# keyboard.net
KiCad netlist of a schematic drawn in Altium Designer
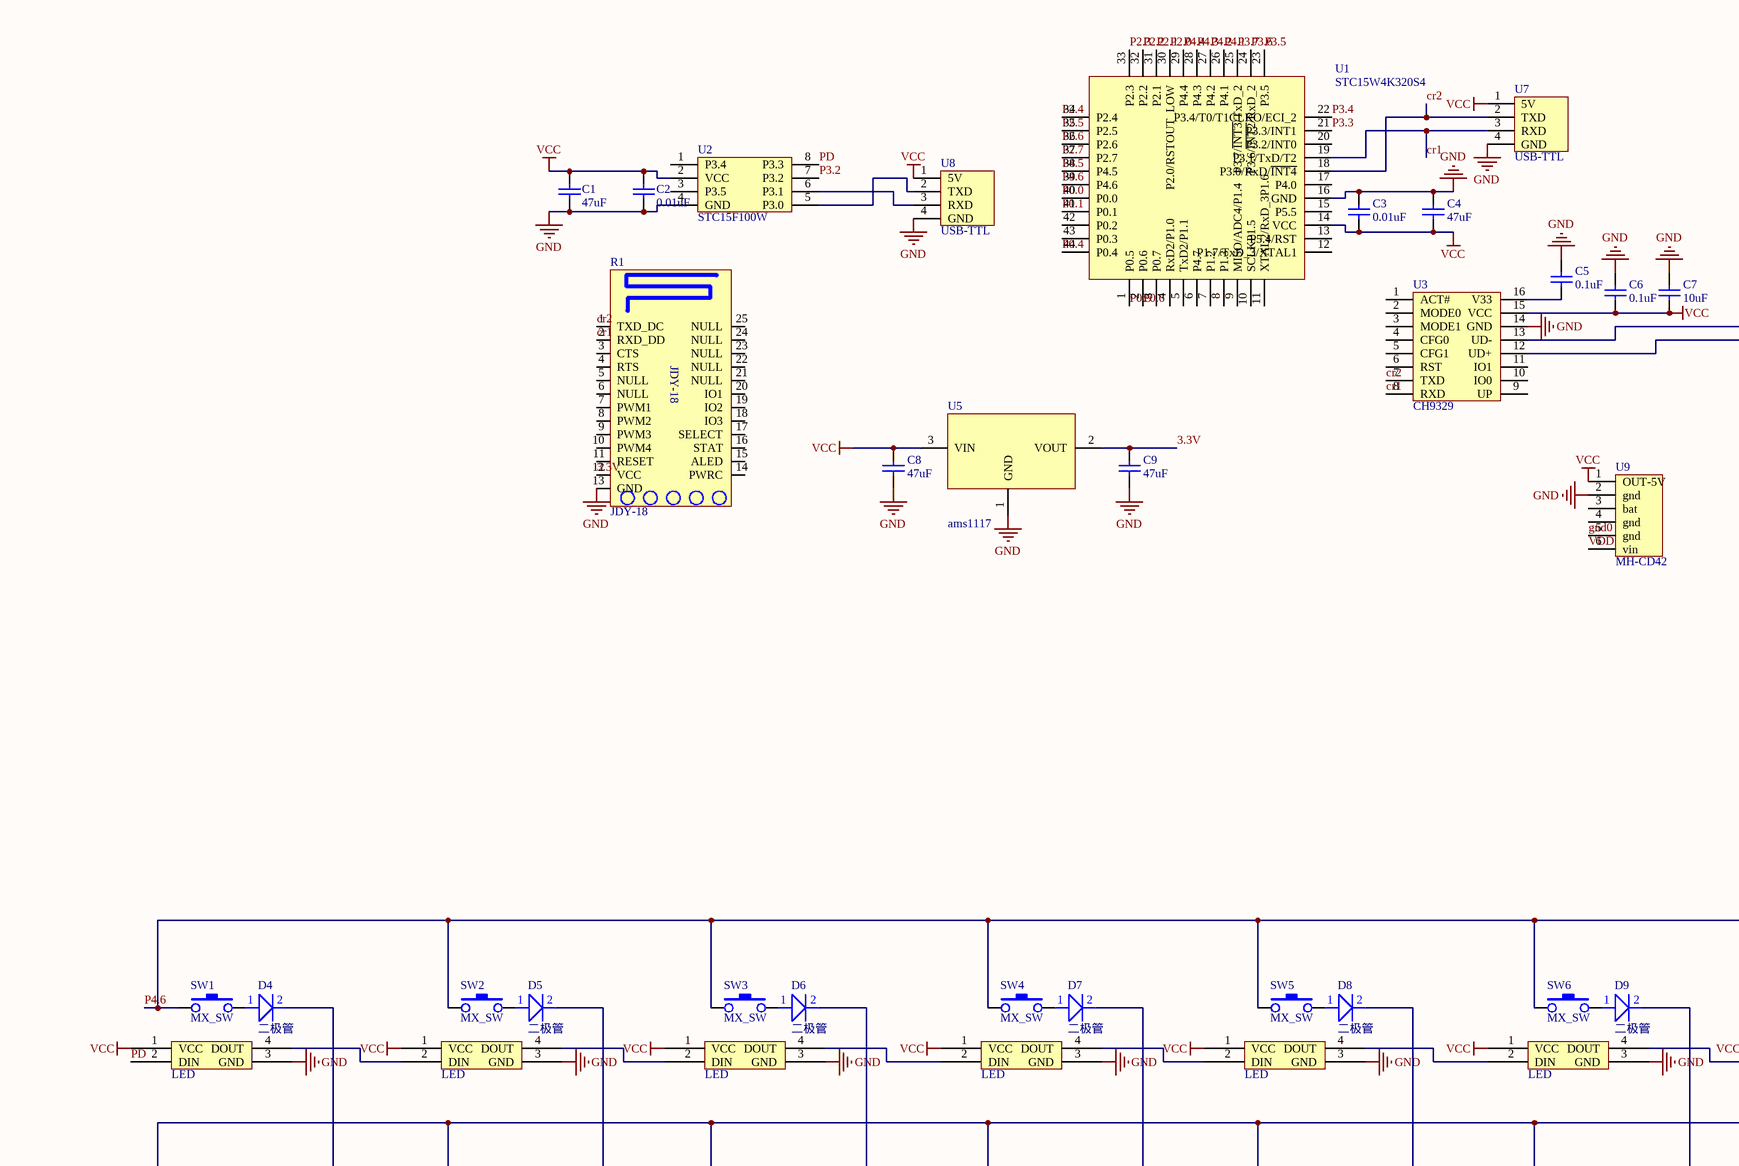
[diagram p0: keyboard.SchDoc, top left]
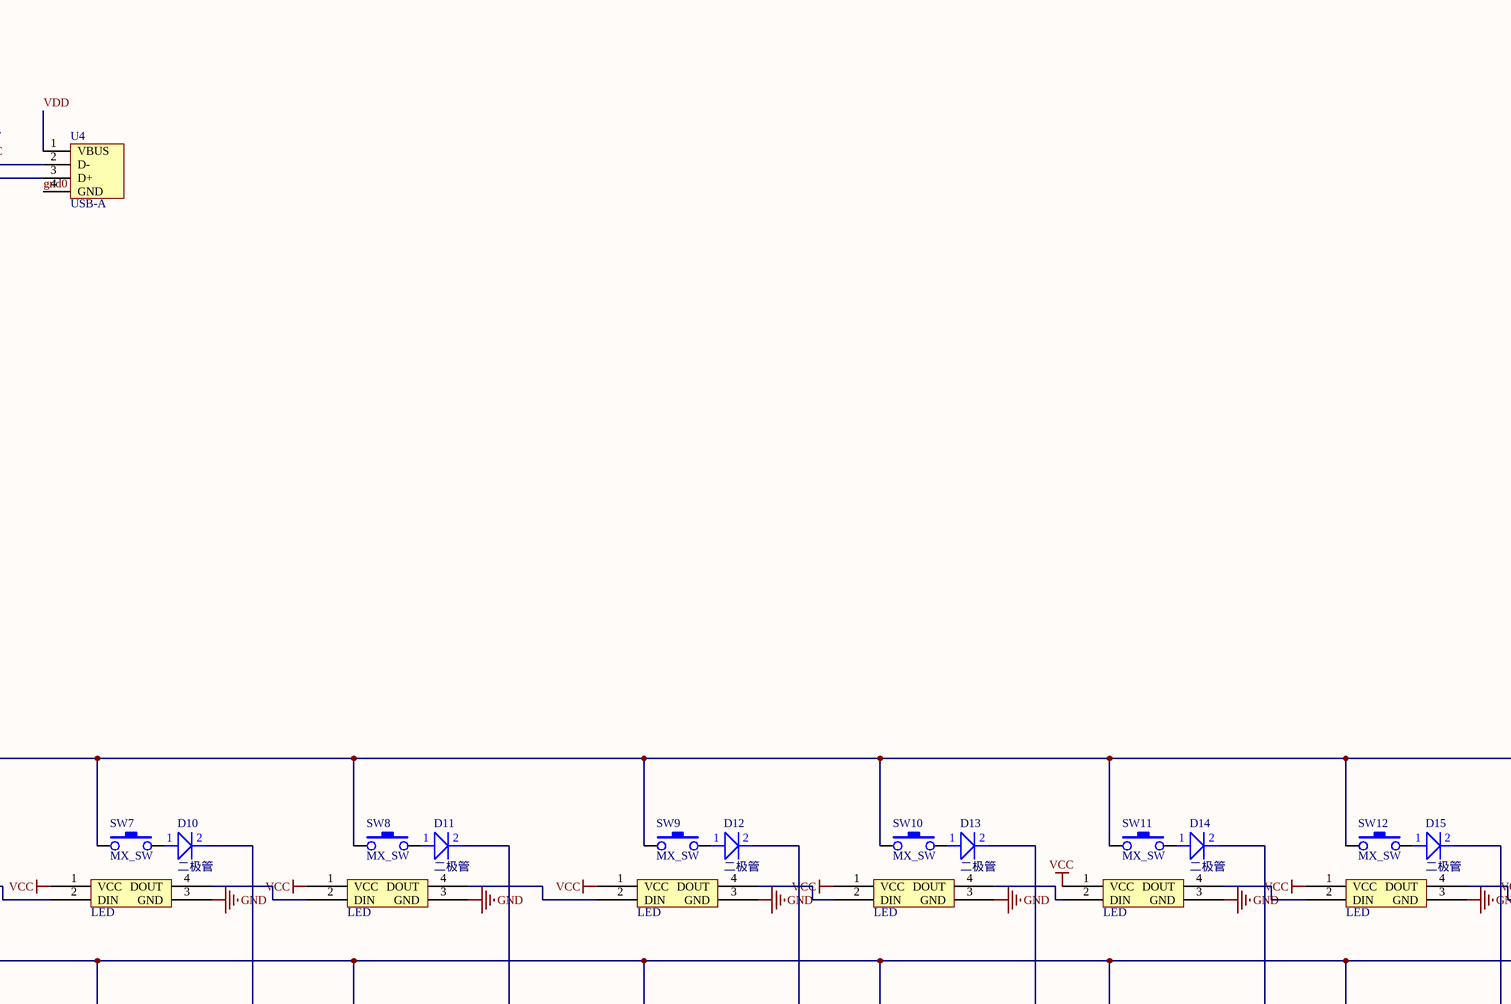
[diagram p1: keyboard.SchDoc, top middle]
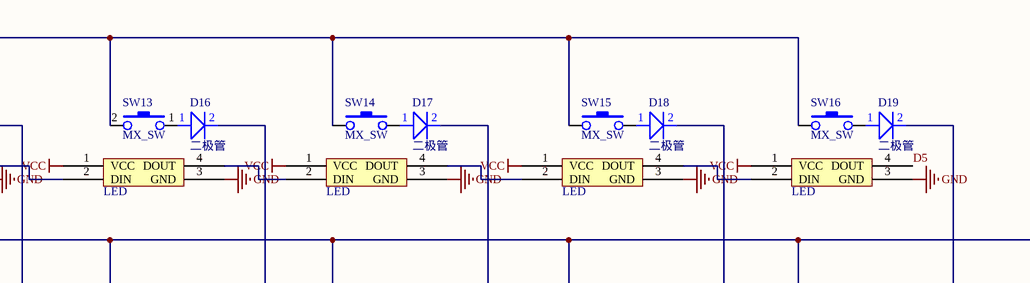
[diagram p2: keyboard.SchDoc, top right]
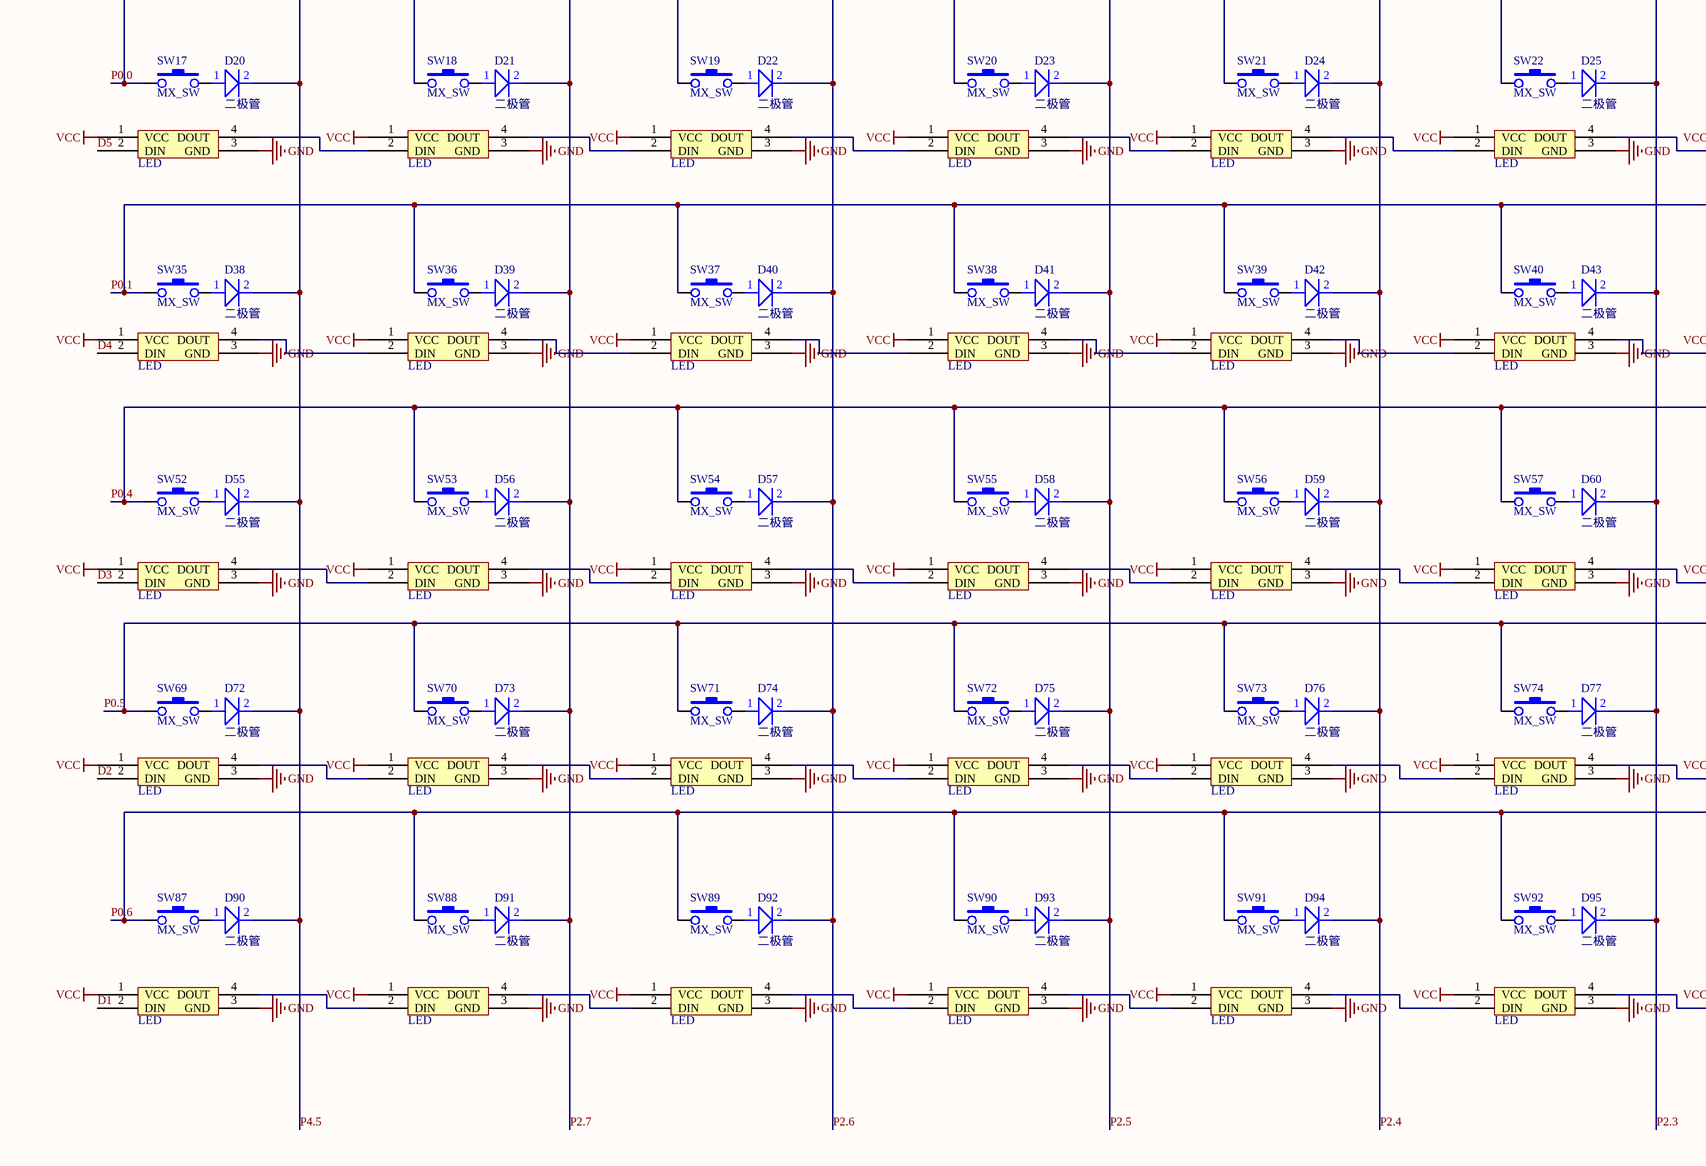
[diagram p3: keyboard.SchDoc, bottom left]
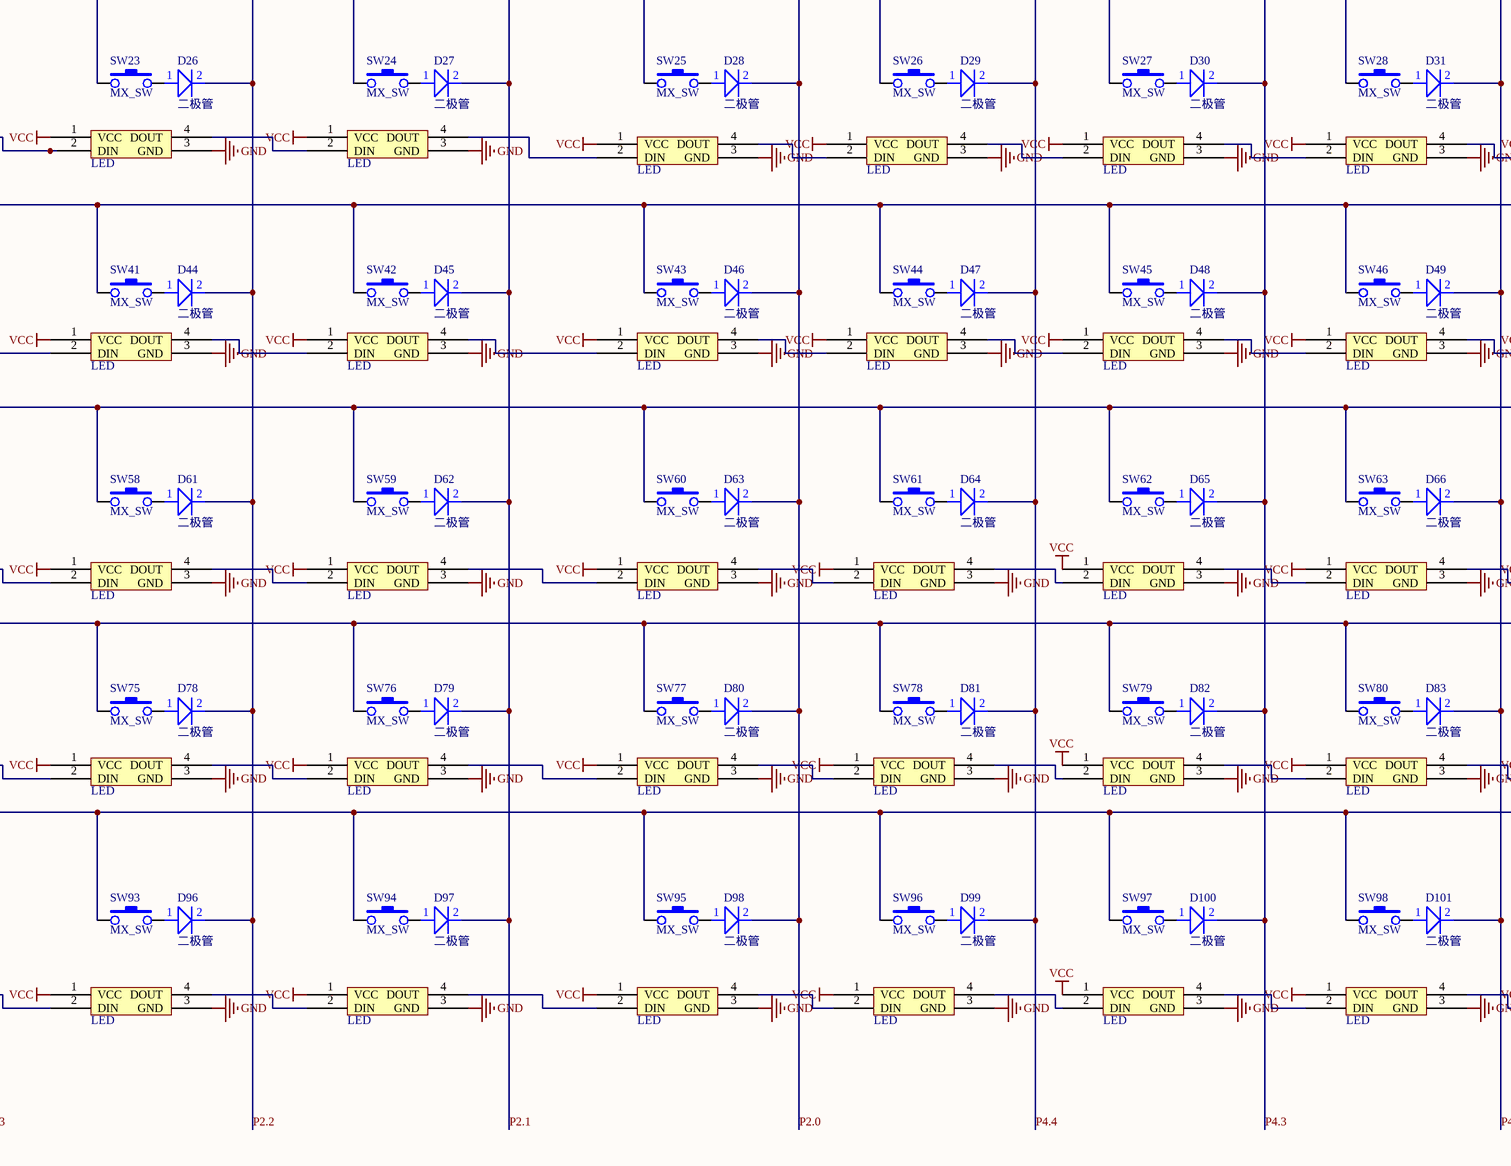
[diagram p4: keyboard.SchDoc, bottom middle]
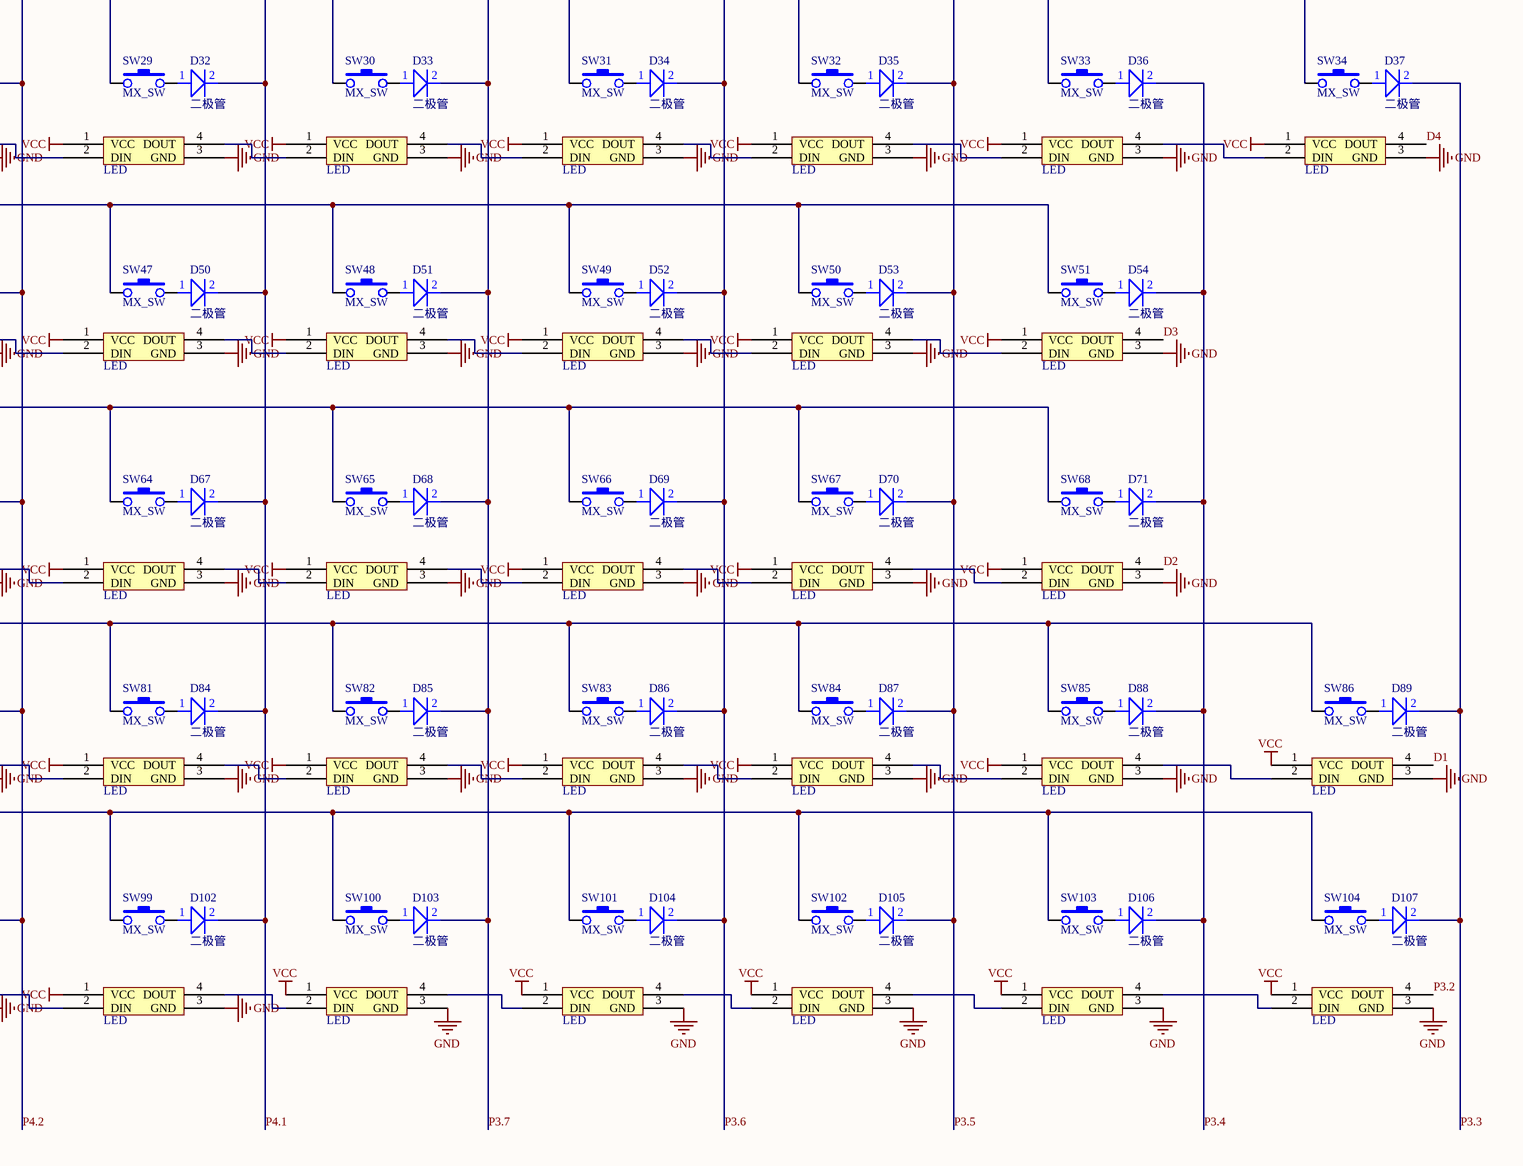
[diagram p5: keyboard.SchDoc, bottom right]

(export (version "E")
  (design (tool "Eeschema 10.0.6"))
  (components
    (comp (ref "*1") (value "LED") (footprint "6028") (libsource (lib "KeyBoard") (part "3512led")))
    (comp (ref "*2") (value "LED") (footprint "6028") (libsource (lib "KeyBoard") (part "3512led")))
    (comp (ref "*3") (value "LED") (footprint "6028") (libsource (lib "KeyBoard") (part "3512led")))
    (comp (ref "*4") (value "LED") (footprint "6028") (libsource (lib "KeyBoard") (part "3512led")))
    (comp (ref "*5") (value "LED") (footprint "6028") (libsource (lib "KeyBoard") (part "3512led")))
    (comp (ref "*6") (value "LED") (footprint "6028") (libsource (lib "KeyBoard") (part "3512led")))
    (comp (ref "*7") (value "LED") (footprint "6028") (libsource (lib "KeyBoard") (part "3512led")))
    (comp (ref "*8") (value "LED") (footprint "6028") (libsource (lib "KeyBoard") (part "3512led")))
    (comp (ref "*9") (value "LED") (footprint "6028") (libsource (lib "KeyBoard") (part "3512led")))
    (comp (ref "*10") (value "LED") (footprint "6028") (libsource (lib "KeyBoard") (part "3512led")))
    (comp (ref "*11") (value "LED") (footprint "6028") (libsource (lib "KeyBoard") (part "3512led")))
    (comp (ref "*12") (value "LED") (footprint "6028") (libsource (lib "KeyBoard") (part "3512led")))
    (comp (ref "*13") (value "LED") (footprint "6028") (libsource (lib "KeyBoard") (part "3512led")))
    (comp (ref "*14") (value "LED") (footprint "6028") (libsource (lib "KeyBoard") (part "3512led")))
    (comp (ref "*15") (value "LED") (footprint "6028") (libsource (lib "KeyBoard") (part "3512led")))
    (comp (ref "*16") (value "LED") (footprint "6028") (libsource (lib "KeyBoard") (part "3512led")))
    (comp (ref "*17") (value "LED") (footprint "6028") (libsource (lib "KeyBoard") (part "3512led")))
    (comp (ref "*18") (value "LED") (footprint "6028") (libsource (lib "KeyBoard") (part "3512led")))
    (comp (ref "*19") (value "LED") (footprint "6028") (libsource (lib "KeyBoard") (part "3512led")))
    (comp (ref "*20") (value "LED") (footprint "6028") (libsource (lib "KeyBoard") (part "3512led")))
    (comp (ref "*21") (value "LED") (footprint "6028") (libsource (lib "KeyBoard") (part "3512led")))
    (comp (ref "*22") (value "LED") (footprint "6028") (libsource (lib "KeyBoard") (part "3512led")))
    (comp (ref "*23") (value "LED") (footprint "6028") (libsource (lib "KeyBoard") (part "3512led")))
    (comp (ref "*24") (value "LED") (footprint "6028") (libsource (lib "KeyBoard") (part "3512led")))
    (comp (ref "*25") (value "LED") (footprint "6028") (libsource (lib "KeyBoard") (part "3512led")))
    (comp (ref "*26") (value "LED") (footprint "6028") (libsource (lib "KeyBoard") (part "3512led")))
    (comp (ref "*27") (value "LED") (footprint "6028") (libsource (lib "KeyBoard") (part "3512led")))
    (comp (ref "*28") (value "LED") (footprint "6028") (libsource (lib "KeyBoard") (part "3512led")))
    (comp (ref "*29") (value "LED") (footprint "6028") (libsource (lib "KeyBoard") (part "3512led")))
    (comp (ref "*30") (value "LED") (footprint "6028") (libsource (lib "KeyBoard") (part "3512led")))
    (comp (ref "*31") (value "LED") (footprint "6028") (libsource (lib "KeyBoard") (part "3512led")))
    (comp (ref "*32") (value "LED") (footprint "6028") (libsource (lib "KeyBoard") (part "3512led")))
    (comp (ref "*33") (value "LED") (footprint "6028") (libsource (lib "KeyBoard") (part "3512led")))
    (comp (ref "*34") (value "LED") (footprint "6028") (libsource (lib "KeyBoard") (part "3512led")))
    (comp (ref "*35") (value "LED") (footprint "6028") (libsource (lib "KeyBoard") (part "3512led")))
    (comp (ref "*36") (value "LED") (footprint "6028") (libsource (lib "KeyBoard") (part "3512led")))
    (comp (ref "*37") (value "LED") (footprint "6028") (libsource (lib "KeyBoard") (part "3512led")))
    (comp (ref "*38") (value "LED") (footprint "6028") (libsource (lib "KeyBoard") (part "3512led")))
    (comp (ref "*39") (value "LED") (footprint "6028") (libsource (lib "KeyBoard") (part "3512led")))
    (comp (ref "*40") (value "LED") (footprint "6028") (libsource (lib "KeyBoard") (part "3512led")))
    (comp (ref "*41") (value "LED") (footprint "6028") (libsource (lib "KeyBoard") (part "3512led")))
    (comp (ref "*42") (value "LED") (footprint "6028") (libsource (lib "KeyBoard") (part "3512led")))
    (comp (ref "*43") (value "LED") (footprint "6028") (libsource (lib "KeyBoard") (part "3512led")))
    (comp (ref "*44") (value "LED") (footprint "6028") (libsource (lib "KeyBoard") (part "3512led")))
    (comp (ref "*45") (value "LED") (footprint "6028") (libsource (lib "KeyBoard") (part "3512led")))
    (comp (ref "*46") (value "LED") (footprint "6028") (libsource (lib "KeyBoard") (part "3512led")))
    (comp (ref "*47") (value "LED") (footprint "6028") (libsource (lib "KeyBoard") (part "3512led")))
    (comp (ref "*48") (value "LED") (footprint "6028") (libsource (lib "KeyBoard") (part "3512led")))
    (comp (ref "*49") (value "LED") (footprint "6028") (libsource (lib "KeyBoard") (part "3512led")))
    (comp (ref "*50") (value "LED") (footprint "6028") (libsource (lib "KeyBoard") (part "3512led")))
    (comp (ref "*51") (value "LED") (footprint "6028") (libsource (lib "KeyBoard") (part "3512led")))
    (comp (ref "*52") (value "LED") (footprint "6028") (libsource (lib "KeyBoard") (part "3512led")))
    (comp (ref "*53") (value "LED") (footprint "6028") (libsource (lib "KeyBoard") (part "3512led")))
    (comp (ref "*54") (value "LED") (footprint "6028") (libsource (lib "KeyBoard") (part "3512led")))
    (comp (ref "*55") (value "LED") (footprint "6028") (libsource (lib "KeyBoard") (part "3512led")))
    (comp (ref "*56") (value "LED") (footprint "6028") (libsource (lib "KeyBoard") (part "3512led")))
    (comp (ref "*57") (value "LED") (footprint "6028") (libsource (lib "KeyBoard") (part "3512led")))
    (comp (ref "*58") (value "LED") (footprint "6028") (libsource (lib "KeyBoard") (part "3512led")))
    (comp (ref "*59") (value "LED") (footprint "6028") (libsource (lib "KeyBoard") (part "3512led")))
    (comp (ref "*60") (value "LED") (footprint "6028") (libsource (lib "KeyBoard") (part "3512led")))
    (comp (ref "*61") (value "LED") (footprint "6028") (libsource (lib "KeyBoard") (part "3512led")))
    (comp (ref "*62") (value "LED") (footprint "6028") (libsource (lib "KeyBoard") (part "3512led")))
    (comp (ref "*63") (value "LED") (footprint "6028") (libsource (lib "KeyBoard") (part "3512led")))
    (comp (ref "*64") (value "LED") (footprint "6028") (libsource (lib "KeyBoard") (part "3512led")))
    (comp (ref "*65") (value "LED") (footprint "6028") (libsource (lib "KeyBoard") (part "3512led")))
    (comp (ref "*66") (value "LED") (footprint "6028") (libsource (lib "KeyBoard") (part "3512led")))
    (comp (ref "*67") (value "LED") (footprint "6028") (libsource (lib "KeyBoard") (part "3512led")))
    (comp (ref "*68") (value "LED") (footprint "6028") (libsource (lib "KeyBoard") (part "3512led")))
    (comp (ref "*69") (value "LED") (footprint "6028") (libsource (lib "KeyBoard") (part "3512led")))
    (comp (ref "*70") (value "LED") (footprint "6028") (libsource (lib "KeyBoard") (part "3512led")))
    (comp (ref "*71") (value "LED") (footprint "6028") (libsource (lib "KeyBoard") (part "3512led")))
    (comp (ref "*72") (value "LED") (footprint "6028") (libsource (lib "KeyBoard") (part "3512led")))
    (comp (ref "*73") (value "LED") (footprint "6028") (libsource (lib "KeyBoard") (part "3512led")))
    (comp (ref "*74") (value "LED") (footprint "6028") (libsource (lib "KeyBoard") (part "3512led")))
    (comp (ref "*75") (value "LED") (footprint "6028") (libsource (lib "KeyBoard") (part "3512led")))
    (comp (ref "*76") (value "LED") (footprint "6028") (libsource (lib "KeyBoard") (part "3512led")))
    (comp (ref "*77") (value "LED") (footprint "6028") (libsource (lib "KeyBoard") (part "3512led")))
    (comp (ref "*78") (value "LED") (footprint "6028") (libsource (lib "KeyBoard") (part "3512led")))
    (comp (ref "*79") (value "LED") (footprint "6028") (libsource (lib "KeyBoard") (part "3512led")))
    (comp (ref "*80") (value "LED") (footprint "6028") (libsource (lib "KeyBoard") (part "3512led")))
    (comp (ref "*81") (value "LED") (footprint "6028") (libsource (lib "KeyBoard") (part "3512led")))
    (comp (ref "*82") (value "LED") (footprint "6028") (libsource (lib "KeyBoard") (part "3512led")))
    (comp (ref "*83") (value "LED") (footprint "6028") (libsource (lib "KeyBoard") (part "3512led")))
    (comp (ref "*84") (value "LED") (footprint "6028") (libsource (lib "KeyBoard") (part "3512led")))
    (comp (ref "*85") (value "LED") (footprint "6028") (libsource (lib "KeyBoard") (part "3512led")))
    (comp (ref "*86") (value "LED") (footprint "6028") (libsource (lib "KeyBoard") (part "3512led")))
    (comp (ref "*87") (value "LED") (footprint "6028") (libsource (lib "KeyBoard") (part "3512led")))
    (comp (ref "*88") (value "LED") (footprint "6028") (libsource (lib "KeyBoard") (part "3512led")))
    (comp (ref "*89") (value "LED") (footprint "6028") (libsource (lib "KeyBoard") (part "3512led")))
    (comp (ref "*90") (value "LED") (footprint "6028") (libsource (lib "KeyBoard") (part "3512led")))
    (comp (ref "*91") (value "LED") (footprint "6028") (libsource (lib "KeyBoard") (part "3512led")))
    (comp (ref "*92") (value "LED") (footprint "6028") (libsource (lib "KeyBoard") (part "3512led")))
    (comp (ref "*93") (value "LED") (footprint "6028") (libsource (lib "KeyBoard") (part "3512led")))
    (comp (ref "*94") (value "LED") (footprint "6028") (libsource (lib "KeyBoard") (part "3512led")))
    (comp (ref "*95") (value "LED") (footprint "6028") (libsource (lib "KeyBoard") (part "3512led")))
    (comp (ref "*96") (value "LED") (footprint "6028") (libsource (lib "KeyBoard") (part "3512led")))
    (comp (ref "*97") (value "LED") (footprint "6028") (libsource (lib "KeyBoard") (part "3512led")))
    (comp (ref "*98") (value "LED") (footprint "6028") (libsource (lib "KeyBoard") (part "3512led")))
    (comp (ref "*99") (value "LED") (footprint "6028") (libsource (lib "KeyBoard") (part "3512led")))
    (comp (ref "*100") (value "LED") (footprint "6028") (libsource (lib "KeyBoard") (part "3512led")))
    (comp (ref "*101") (value "LED") (footprint "6028") (libsource (lib "KeyBoard") (part "3512led")))
    (comp (ref "*102") (value "LED") (footprint "6028") (libsource (lib "KeyBoard") (part "3512led")))
    (comp (ref "*103") (value "LED") (footprint "6028") (libsource (lib "KeyBoard") (part "3512led")))
    (comp (ref "*104") (value "LED") (footprint "6028") (libsource (lib "KeyBoard") (part "3512led")))
    (comp (ref "C1")
      (value "47uF")
      (footprint "C 0805_M")
      (fields (field (name "Comment") "C_0603") (field (name "PUBLISHER") "Altium Limited"))
      (libsource (lib "RoboFly") (part "C_0603"))
    )
    (comp (ref "C2")
      (value "0.01uF")
      (footprint "C 0805_M")
      (fields (field (name "Comment") "C_0603") (field (name "PUBLISHER") "Altium Limited"))
      (libsource (lib "RoboFly") (part "C_0603"))
    )
    (comp (ref "C3")
      (value "0.01uF")
      (footprint "C 0805_M")
      (fields (field (name "Comment") "C_0603") (field (name "PUBLISHER") "Altium Limited"))
      (libsource (lib "RoboFly") (part "C_0603"))
    )
    (comp (ref "C4")
      (value "47uF")
      (footprint "C 0805_M")
      (fields (field (name "Comment") "C_0603") (field (name "PUBLISHER") "Altium Limited"))
      (libsource (lib "RoboFly") (part "C_0603"))
    )
    (comp (ref "C5")
      (value "0.1uF")
      (footprint "C 0805_M")
      (fields (field (name "Comment") "C_0603") (field (name "PUBLISHER") "Altium Limited"))
      (libsource (lib "RoboFly") (part "C_0603"))
    )
    (comp (ref "C6")
      (value "0.1uF")
      (footprint "C 0805_M")
      (fields (field (name "Comment") "C_0603") (field (name "PUBLISHER") "Altium Limited"))
      (libsource (lib "RoboFly") (part "C_0603"))
    )
    (comp (ref "C7")
      (value "10uF")
      (footprint "C 0805_M")
      (fields (field (name "Comment") "C_0603") (field (name "PUBLISHER") "Altium Limited"))
      (libsource (lib "RoboFly") (part "C_0603"))
    )
    (comp (ref "C8")
      (value "47uF")
      (footprint "C 0805_M")
      (fields (field (name "Comment") "C_0603") (field (name "PUBLISHER") "Altium Limited"))
      (libsource (lib "RoboFly") (part "C_0603"))
    )
    (comp (ref "C9")
      (value "47uF")
      (footprint "C 0805_M")
      (fields (field (name "Comment") "C_0603") (field (name "PUBLISHER") "Altium Limited"))
      (libsource (lib "RoboFly") (part "C_0603"))
    )
    (comp (ref "D4") (value "二极管") (footprint "LL-34") (libsource (lib "KeyBoard") (part "LL4148")))
    (comp (ref "D5") (value "二极管") (footprint "LL-34") (libsource (lib "KeyBoard") (part "LL4148")))
    (comp (ref "D6") (value "二极管") (footprint "LL-34") (libsource (lib "KeyBoard") (part "LL4148")))
    (comp (ref "D7") (value "二极管") (footprint "LL-34") (libsource (lib "KeyBoard") (part "LL4148")))
    (comp (ref "D8") (value "二极管") (footprint "LL-34") (libsource (lib "KeyBoard") (part "LL4148")))
    (comp (ref "D9") (value "二极管") (footprint "LL-34") (libsource (lib "KeyBoard") (part "LL4148")))
    (comp (ref "D10") (value "二极管") (footprint "LL-34") (libsource (lib "KeyBoard") (part "LL4148")))
    (comp (ref "D11") (value "二极管") (footprint "LL-34") (libsource (lib "KeyBoard") (part "LL4148")))
    (comp (ref "D12") (value "二极管") (footprint "LL-34") (libsource (lib "KeyBoard") (part "LL4148")))
    (comp (ref "D13") (value "二极管") (footprint "LL-34") (libsource (lib "KeyBoard") (part "LL4148")))
    (comp (ref "D14") (value "二极管") (footprint "LL-34") (libsource (lib "KeyBoard") (part "LL4148")))
    (comp (ref "D15") (value "二极管") (footprint "LL-34") (libsource (lib "KeyBoard") (part "LL4148")))
    (comp (ref "D16") (value "二极管") (footprint "LL-34") (libsource (lib "KeyBoard") (part "LL4148")))
    (comp (ref "D17") (value "二极管") (footprint "LL-34") (libsource (lib "KeyBoard") (part "LL4148")))
    (comp (ref "D18") (value "二极管") (footprint "LL-34") (libsource (lib "KeyBoard") (part "LL4148")))
    (comp (ref "D19") (value "二极管") (footprint "LL-34") (libsource (lib "KeyBoard") (part "LL4148")))
    (comp (ref "D20") (value "二极管") (footprint "LL-34") (libsource (lib "KeyBoard") (part "LL4148")))
    (comp (ref "D21") (value "二极管") (footprint "LL-34") (libsource (lib "KeyBoard") (part "LL4148")))
    (comp (ref "D22") (value "二极管") (footprint "LL-34") (libsource (lib "KeyBoard") (part "LL4148")))
    (comp (ref "D23") (value "二极管") (footprint "LL-34") (libsource (lib "KeyBoard") (part "LL4148")))
    (comp (ref "D24") (value "二极管") (footprint "LL-34") (libsource (lib "KeyBoard") (part "LL4148")))
    (comp (ref "D25") (value "二极管") (footprint "LL-34") (libsource (lib "KeyBoard") (part "LL4148")))
    (comp (ref "D26") (value "二极管") (footprint "LL-34") (libsource (lib "KeyBoard") (part "LL4148")))
    (comp (ref "D27") (value "二极管") (footprint "LL-34") (libsource (lib "KeyBoard") (part "LL4148")))
    (comp (ref "D28") (value "二极管") (footprint "LL-34") (libsource (lib "KeyBoard") (part "LL4148")))
    (comp (ref "D29") (value "二极管") (footprint "LL-34") (libsource (lib "KeyBoard") (part "LL4148")))
    (comp (ref "D30") (value "二极管") (footprint "LL-34") (libsource (lib "KeyBoard") (part "LL4148")))
    (comp (ref "D31") (value "二极管") (footprint "LL-34") (libsource (lib "KeyBoard") (part "LL4148")))
    (comp (ref "D32") (value "二极管") (footprint "LL-34") (libsource (lib "KeyBoard") (part "LL4148")))
    (comp (ref "D33") (value "二极管") (footprint "LL-34") (libsource (lib "KeyBoard") (part "LL4148")))
    (comp (ref "D34") (value "二极管") (footprint "LL-34") (libsource (lib "KeyBoard") (part "LL4148")))
    (comp (ref "D35") (value "二极管") (footprint "LL-34") (libsource (lib "KeyBoard") (part "LL4148")))
    (comp (ref "D36") (value "二极管") (footprint "LL-34") (libsource (lib "KeyBoard") (part "LL4148")))
    (comp (ref "D37") (value "二极管") (footprint "LL-34") (libsource (lib "KeyBoard") (part "LL4148")))
    (comp (ref "D38") (value "二极管") (footprint "LL-34") (libsource (lib "KeyBoard") (part "LL4148")))
    (comp (ref "D39") (value "二极管") (footprint "LL-34") (libsource (lib "KeyBoard") (part "LL4148")))
    (comp (ref "D40") (value "二极管") (footprint "LL-34") (libsource (lib "KeyBoard") (part "LL4148")))
    (comp (ref "D41") (value "二极管") (footprint "LL-34") (libsource (lib "KeyBoard") (part "LL4148")))
    (comp (ref "D42") (value "二极管") (footprint "LL-34") (libsource (lib "KeyBoard") (part "LL4148")))
    (comp (ref "D43") (value "二极管") (footprint "LL-34") (libsource (lib "KeyBoard") (part "LL4148")))
    (comp (ref "D44") (value "二极管") (footprint "LL-34") (libsource (lib "KeyBoard") (part "LL4148")))
    (comp (ref "D45") (value "二极管") (footprint "LL-34") (libsource (lib "KeyBoard") (part "LL4148")))
    (comp (ref "D46") (value "二极管") (footprint "LL-34") (libsource (lib "KeyBoard") (part "LL4148")))
    (comp (ref "D47") (value "二极管") (footprint "LL-34") (libsource (lib "KeyBoard") (part "LL4148")))
    (comp (ref "D48") (value "二极管") (footprint "LL-34") (libsource (lib "KeyBoard") (part "LL4148")))
    (comp (ref "D49") (value "二极管") (footprint "LL-34") (libsource (lib "KeyBoard") (part "LL4148")))
    (comp (ref "D50") (value "二极管") (footprint "LL-34") (libsource (lib "KeyBoard") (part "LL4148")))
    (comp (ref "D51") (value "二极管") (footprint "LL-34") (libsource (lib "KeyBoard") (part "LL4148")))
    (comp (ref "D52") (value "二极管") (footprint "LL-34") (libsource (lib "KeyBoard") (part "LL4148")))
    (comp (ref "D53") (value "二极管") (footprint "LL-34") (libsource (lib "KeyBoard") (part "LL4148")))
    (comp (ref "D54") (value "二极管") (footprint "LL-34") (libsource (lib "KeyBoard") (part "LL4148")))
    (comp (ref "D55") (value "二极管") (footprint "LL-34") (libsource (lib "KeyBoard") (part "LL4148")))
    (comp (ref "D56") (value "二极管") (footprint "LL-34") (libsource (lib "KeyBoard") (part "LL4148")))
    (comp (ref "D57") (value "二极管") (footprint "LL-34") (libsource (lib "KeyBoard") (part "LL4148")))
    (comp (ref "D58") (value "二极管") (footprint "LL-34") (libsource (lib "KeyBoard") (part "LL4148")))
    (comp (ref "D59") (value "二极管") (footprint "LL-34") (libsource (lib "KeyBoard") (part "LL4148")))
    (comp (ref "D60") (value "二极管") (footprint "LL-34") (libsource (lib "KeyBoard") (part "LL4148")))
    (comp (ref "D61") (value "二极管") (footprint "LL-34") (libsource (lib "KeyBoard") (part "LL4148")))
    (comp (ref "D62") (value "二极管") (footprint "LL-34") (libsource (lib "KeyBoard") (part "LL4148")))
    (comp (ref "D63") (value "二极管") (footprint "LL-34") (libsource (lib "KeyBoard") (part "LL4148")))
    (comp (ref "D64") (value "二极管") (footprint "LL-34") (libsource (lib "KeyBoard") (part "LL4148")))
    (comp (ref "D65") (value "二极管") (footprint "LL-34") (libsource (lib "KeyBoard") (part "LL4148")))
    (comp (ref "D66") (value "二极管") (footprint "LL-34") (libsource (lib "KeyBoard") (part "LL4148")))
    (comp (ref "D67") (value "二极管") (footprint "LL-34") (libsource (lib "KeyBoard") (part "LL4148")))
    (comp (ref "D68") (value "二极管") (footprint "LL-34") (libsource (lib "KeyBoard") (part "LL4148")))
    (comp (ref "D69") (value "二极管") (footprint "LL-34") (libsource (lib "KeyBoard") (part "LL4148")))
    (comp (ref "D70") (value "二极管") (footprint "LL-34") (libsource (lib "KeyBoard") (part "LL4148")))
    (comp (ref "D71") (value "二极管") (footprint "LL-34") (libsource (lib "KeyBoard") (part "LL4148")))
    (comp (ref "D72") (value "二极管") (footprint "LL-34") (libsource (lib "KeyBoard") (part "LL4148")))
    (comp (ref "D73") (value "二极管") (footprint "LL-34") (libsource (lib "KeyBoard") (part "LL4148")))
    (comp (ref "D74") (value "二极管") (footprint "LL-34") (libsource (lib "KeyBoard") (part "LL4148")))
    (comp (ref "D75") (value "二极管") (footprint "LL-34") (libsource (lib "KeyBoard") (part "LL4148")))
    (comp (ref "D76") (value "二极管") (footprint "LL-34") (libsource (lib "KeyBoard") (part "LL4148")))
    (comp (ref "D77") (value "二极管") (footprint "LL-34") (libsource (lib "KeyBoard") (part "LL4148")))
    (comp (ref "D78") (value "二极管") (footprint "LL-34") (libsource (lib "KeyBoard") (part "LL4148")))
    (comp (ref "D79") (value "二极管") (footprint "LL-34") (libsource (lib "KeyBoard") (part "LL4148")))
    (comp (ref "D80") (value "二极管") (footprint "LL-34") (libsource (lib "KeyBoard") (part "LL4148")))
    (comp (ref "D81") (value "二极管") (footprint "LL-34") (libsource (lib "KeyBoard") (part "LL4148")))
    (comp (ref "D82") (value "二极管") (footprint "LL-34") (libsource (lib "KeyBoard") (part "LL4148")))
    (comp (ref "D83") (value "二极管") (footprint "LL-34") (libsource (lib "KeyBoard") (part "LL4148")))
    (comp (ref "D84") (value "二极管") (footprint "LL-34") (libsource (lib "KeyBoard") (part "LL4148")))
    (comp (ref "D85") (value "二极管") (footprint "LL-34") (libsource (lib "KeyBoard") (part "LL4148")))
    (comp (ref "D86") (value "二极管") (footprint "LL-34") (libsource (lib "KeyBoard") (part "LL4148")))
    (comp (ref "D87") (value "二极管") (footprint "LL-34") (libsource (lib "KeyBoard") (part "LL4148")))
    (comp (ref "D88") (value "二极管") (footprint "LL-34") (libsource (lib "KeyBoard") (part "LL4148")))
    (comp (ref "D89") (value "二极管") (footprint "LL-34") (libsource (lib "KeyBoard") (part "LL4148")))
    (comp (ref "D90") (value "二极管") (footprint "LL-34") (libsource (lib "KeyBoard") (part "LL4148")))
    (comp (ref "D91") (value "二极管") (footprint "LL-34") (libsource (lib "KeyBoard") (part "LL4148")))
    (comp (ref "D92") (value "二极管") (footprint "LL-34") (libsource (lib "KeyBoard") (part "LL4148")))
    (comp (ref "D93") (value "二极管") (footprint "LL-34") (libsource (lib "KeyBoard") (part "LL4148")))
    (comp (ref "D94") (value "二极管") (footprint "LL-34") (libsource (lib "KeyBoard") (part "LL4148")))
    (comp (ref "D95") (value "二极管") (footprint "LL-34") (libsource (lib "KeyBoard") (part "LL4148")))
    (comp (ref "D96") (value "二极管") (footprint "LL-34") (libsource (lib "KeyBoard") (part "LL4148")))
    (comp (ref "D97") (value "二极管") (footprint "LL-34") (libsource (lib "KeyBoard") (part "LL4148")))
    (comp (ref "D98") (value "二极管") (footprint "LL-34") (libsource (lib "KeyBoard") (part "LL4148")))
    (comp (ref "D99") (value "二极管") (footprint "LL-34") (libsource (lib "KeyBoard") (part "LL4148")))
    (comp (ref "D100") (value "二极管") (footprint "LL-34") (libsource (lib "KeyBoard") (part "LL4148")))
    (comp (ref "D101") (value "二极管") (footprint "LL-34") (libsource (lib "KeyBoard") (part "LL4148")))
    (comp (ref "D102") (value "二极管") (footprint "LL-34") (libsource (lib "KeyBoard") (part "LL4148")))
    (comp (ref "D103") (value "二极管") (footprint "LL-34") (libsource (lib "KeyBoard") (part "LL4148")))
    (comp (ref "D104") (value "二极管") (footprint "LL-34") (libsource (lib "KeyBoard") (part "LL4148")))
    (comp (ref "D105") (value "二极管") (footprint "LL-34") (libsource (lib "KeyBoard") (part "LL4148")))
    (comp (ref "D106") (value "二极管") (footprint "LL-34") (libsource (lib "KeyBoard") (part "LL4148")))
    (comp (ref "D107") (value "二极管") (footprint "LL-34") (libsource (lib "KeyBoard") (part "LL4148")))
    (comp (ref "R1") (value "JDY-18") (footprint "JDY-18") (libsource (lib "*") (part "JDY-18")))
    (comp (ref "SW1")
      (value "MX_SW")
      (footprint "MX_SW-4")
      (description "with Fixation pins  1-Pole")
      (libsource (lib "KeyBoard") (part "MX_SW-4"))
    )
    (comp (ref "SW2")
      (value "MX_SW")
      (footprint "MX_SW-4")
      (description "with Fixation pins  1-Pole")
      (libsource (lib "KeyBoard") (part "MX_SW-4"))
    )
    (comp (ref "SW3")
      (value "MX_SW")
      (footprint "MX_SW-4")
      (description "with Fixation pins  1-Pole")
      (libsource (lib "KeyBoard") (part "MX_SW-4"))
    )
    (comp (ref "SW4")
      (value "MX_SW")
      (footprint "MX_SW-4")
      (description "with Fixation pins  1-Pole")
      (libsource (lib "KeyBoard") (part "MX_SW-4"))
    )
    (comp (ref "SW5")
      (value "MX_SW")
      (footprint "MX_SW-4")
      (description "with Fixation pins  1-Pole")
      (libsource (lib "KeyBoard") (part "MX_SW-4"))
    )
    (comp (ref "SW6")
      (value "MX_SW")
      (footprint "MX_SW-4")
      (description "with Fixation pins  1-Pole")
      (libsource (lib "KeyBoard") (part "MX_SW-4"))
    )
    (comp (ref "SW7")
      (value "MX_SW")
      (footprint "MX_SW-4")
      (description "with Fixation pins  1-Pole")
      (libsource (lib "KeyBoard") (part "MX_SW-4"))
    )
    (comp (ref "SW8")
      (value "MX_SW")
      (footprint "MX_SW-4")
      (description "with Fixation pins  1-Pole")
      (libsource (lib "KeyBoard") (part "MX_SW-4"))
    )
    (comp (ref "SW9")
      (value "MX_SW")
      (footprint "MX_SW-4")
      (description "with Fixation pins  1-Pole")
      (libsource (lib "KeyBoard") (part "MX_SW-4"))
    )
    (comp (ref "SW10")
      (value "MX_SW")
      (footprint "MX_SW-4")
      (description "with Fixation pins  1-Pole")
      (libsource (lib "KeyBoard") (part "MX_SW-4"))
    )
    (comp (ref "SW11")
      (value "MX_SW")
      (footprint "MX_SW-4")
      (description "with Fixation pins  1-Pole")
      (libsource (lib "KeyBoard") (part "MX_SW-4"))
    )
    (comp (ref "SW12")
      (value "MX_SW")
      (footprint "MX_SW-4")
      (description "with Fixation pins  1-Pole")
      (libsource (lib "KeyBoard") (part "MX_SW-4"))
    )
    (comp (ref "SW13")
      (value "MX_SW")
      (footprint "MX_SW-4")
      (description "with Fixation pins  1-Pole")
      (libsource (lib "") (part "MX_SW-4_1"))
    )
    (comp (ref "SW14")
      (value "MX_SW")
      (footprint "MX_SW-4")
      (description "with Fixation pins  1-Pole")
      (libsource (lib "KeyBoard") (part "MX_SW-4"))
    )
    (comp (ref "SW15")
      (value "MX_SW")
      (footprint "MX_SW-4")
      (description "with Fixation pins  1-Pole")
      (libsource (lib "KeyBoard") (part "MX_SW-4"))
    )
    (comp (ref "SW16")
      (value "MX_SW")
      (footprint "MX_SW-4")
      (description "with Fixation pins  1-Pole")
      (libsource (lib "KeyBoard") (part "MX_SW-4"))
    )
    (comp (ref "SW17")
      (value "MX_SW")
      (footprint "MX_SW-4")
      (description "with Fixation pins  1-Pole")
      (libsource (lib "KeyBoard") (part "MX_SW-4"))
    )
    (comp (ref "SW18")
      (value "MX_SW")
      (footprint "MX_SW-4")
      (description "with Fixation pins  1-Pole")
      (libsource (lib "KeyBoard") (part "MX_SW-4"))
    )
    (comp (ref "SW19")
      (value "MX_SW")
      (footprint "MX_SW-4")
      (description "with Fixation pins  1-Pole")
      (libsource (lib "KeyBoard") (part "MX_SW-4"))
    )
    (comp (ref "SW20")
      (value "MX_SW")
      (footprint "MX_SW-4")
      (description "with Fixation pins  1-Pole")
      (libsource (lib "KeyBoard") (part "MX_SW-4"))
    )
    (comp (ref "SW21")
      (value "MX_SW")
      (footprint "MX_SW-4")
      (description "with Fixation pins  1-Pole")
      (libsource (lib "KeyBoard") (part "MX_SW-4"))
    )
    (comp (ref "SW22")
      (value "MX_SW")
      (footprint "MX_SW-4")
      (description "with Fixation pins  1-Pole")
      (libsource (lib "KeyBoard") (part "MX_SW-4"))
    )
    (comp (ref "SW23")
      (value "MX_SW")
      (footprint "MX_SW-4")
      (description "with Fixation pins  1-Pole")
      (libsource (lib "KeyBoard") (part "MX_SW-4"))
    )
    (comp (ref "SW24")
      (value "MX_SW")
      (footprint "MX_SW-4")
      (description "with Fixation pins  1-Pole")
      (libsource (lib "KeyBoard") (part "MX_SW-4"))
    )
    (comp (ref "SW25")
      (value "MX_SW")
      (footprint "MX_SW-4")
      (description "with Fixation pins  1-Pole")
      (libsource (lib "KeyBoard") (part "MX_SW-4"))
    )
    (comp (ref "SW26")
      (value "MX_SW")
      (footprint "MX_SW-4")
      (description "with Fixation pins  1-Pole")
      (libsource (lib "KeyBoard") (part "MX_SW-4"))
    )
    (comp (ref "SW27")
      (value "MX_SW")
      (footprint "MX_SW-4")
      (description "with Fixation pins  1-Pole")
      (libsource (lib "KeyBoard") (part "MX_SW-4"))
    )
    (comp (ref "SW28")
      (value "MX_SW")
      (footprint "MX_SW-4")
      (description "with Fixation pins  1-Pole")
      (libsource (lib "KeyBoard") (part "MX_SW-4"))
    )
    (comp (ref "SW29")
      (value "MX_SW")
      (footprint "MX_SW-4")
      (description "with Fixation pins  1-Pole")
      (libsource (lib "KeyBoard") (part "MX_SW-4"))
    )
    (comp (ref "SW30")
      (value "MX_SW")
      (footprint "MX_SW-4")
      (description "with Fixation pins  1-Pole")
      (libsource (lib "KeyBoard") (part "MX_SW-4"))
    )
    (comp (ref "SW31")
      (value "MX_SW")
      (footprint "MX_SW-4")
      (description "with Fixation pins  1-Pole")
      (libsource (lib "KeyBoard") (part "MX_SW-4"))
    )
    (comp (ref "SW32")
      (value "MX_SW")
      (footprint "MX_SW-4")
      (description "with Fixation pins  1-Pole")
      (libsource (lib "KeyBoard") (part "MX_SW-4"))
    )
    (comp (ref "SW33")
      (value "MX_SW")
      (footprint "MX_SW-4")
      (description "with Fixation pins  1-Pole")
      (libsource (lib "KeyBoard") (part "MX_SW-4"))
    )
    (comp (ref "SW34")
      (value "MX_SW")
      (footprint "MX_SW-4")
      (description "with Fixation pins  1-Pole")
      (libsource (lib "KeyBoard") (part "MX_SW-4"))
    )
    (comp (ref "SW35")
      (value "MX_SW")
      (footprint "MX_SW-4")
      (description "with Fixation pins  1-Pole")
      (libsource (lib "KeyBoard") (part "MX_SW-4"))
    )
    (comp (ref "SW36")
      (value "MX_SW")
      (footprint "MX_SW-4")
      (description "with Fixation pins  1-Pole")
      (libsource (lib "KeyBoard") (part "MX_SW-4"))
    )
    (comp (ref "SW37")
      (value "MX_SW")
      (footprint "MX_SW-4")
      (description "with Fixation pins  1-Pole")
      (libsource (lib "KeyBoard") (part "MX_SW-4"))
    )
    (comp (ref "SW38")
      (value "MX_SW")
      (footprint "MX_SW-4")
      (description "with Fixation pins  1-Pole")
      (libsource (lib "KeyBoard") (part "MX_SW-4"))
    )
    (comp (ref "SW39")
      (value "MX_SW")
      (footprint "MX_SW-4")
      (description "with Fixation pins  1-Pole")
      (libsource (lib "KeyBoard") (part "MX_SW-4"))
    )
    (comp (ref "SW40")
      (value "MX_SW")
      (footprint "MX_SW-4")
      (description "with Fixation pins  1-Pole")
      (libsource (lib "KeyBoard") (part "MX_SW-4"))
    )
    (comp (ref "SW41")
      (value "MX_SW")
      (footprint "MX_SW-4")
      (description "with Fixation pins  1-Pole")
      (libsource (lib "KeyBoard") (part "MX_SW-4"))
    )
    (comp (ref "SW42")
      (value "MX_SW")
      (footprint "MX_SW-4")
      (description "with Fixation pins  1-Pole")
      (libsource (lib "KeyBoard") (part "MX_SW-4"))
    )
    (comp (ref "SW43")
      (value "MX_SW")
      (footprint "MX_SW-4")
      (description "with Fixation pins  1-Pole")
      (libsource (lib "KeyBoard") (part "MX_SW-4"))
    )
    (comp (ref "SW44")
      (value "MX_SW")
      (footprint "MX_SW-4")
      (description "with Fixation pins  1-Pole")
      (libsource (lib "KeyBoard") (part "MX_SW-4"))
    )
    (comp (ref "SW45")
      (value "MX_SW")
      (footprint "MX_SW-4")
      (description "with Fixation pins  1-Pole")
      (libsource (lib "KeyBoard") (part "MX_SW-4"))
    )
    (comp (ref "SW46")
      (value "MX_SW")
      (footprint "MX_SW-4")
      (description "with Fixation pins  1-Pole")
      (libsource (lib "KeyBoard") (part "MX_SW-4"))
    )
    (comp (ref "SW47")
      (value "MX_SW")
      (footprint "MX_SW-4")
      (description "with Fixation pins  1-Pole")
      (libsource (lib "KeyBoard") (part "MX_SW-4"))
    )
    (comp (ref "SW48")
      (value "MX_SW")
      (footprint "MX_SW-4")
      (description "with Fixation pins  1-Pole")
      (libsource (lib "KeyBoard") (part "MX_SW-4"))
    )
    (comp (ref "SW49")
      (value "MX_SW")
      (footprint "MX_SW-4")
      (description "with Fixation pins  1-Pole")
      (libsource (lib "KeyBoard") (part "MX_SW-4"))
    )
    (comp (ref "SW50")
      (value "MX_SW")
      (footprint "MX_SW-4")
      (description "with Fixation pins  1-Pole")
      (libsource (lib "KeyBoard") (part "MX_SW-4"))
    )
    (comp (ref "SW51")
      (value "MX_SW")
      (footprint "MX_SW-4")
      (description "with Fixation pins  1-Pole")
      (libsource (lib "KeyBoard") (part "MX_SW-4"))
    )
    (comp (ref "SW52")
      (value "MX_SW")
      (footprint "MX_SW-4")
      (description "with Fixation pins  1-Pole")
      (libsource (lib "KeyBoard") (part "MX_SW-4"))
    )
    (comp (ref "SW53")
      (value "MX_SW")
      (footprint "MX_SW-4")
      (description "with Fixation pins  1-Pole")
      (libsource (lib "KeyBoard") (part "MX_SW-4"))
    )
    (comp (ref "SW54")
      (value "MX_SW")
      (footprint "MX_SW-4")
      (description "with Fixation pins  1-Pole")
      (libsource (lib "KeyBoard") (part "MX_SW-4"))
    )
    (comp (ref "SW55")
      (value "MX_SW")
      (footprint "MX_SW-4")
      (description "with Fixation pins  1-Pole")
      (libsource (lib "KeyBoard") (part "MX_SW-4"))
    )
    (comp (ref "SW56")
      (value "MX_SW")
      (footprint "MX_SW-4")
      (description "with Fixation pins  1-Pole")
      (libsource (lib "KeyBoard") (part "MX_SW-4"))
    )
    (comp (ref "SW57")
      (value "MX_SW")
      (footprint "MX_SW-4")
      (description "with Fixation pins  1-Pole")
      (libsource (lib "KeyBoard") (part "MX_SW-4"))
    )
    (comp (ref "SW58")
      (value "MX_SW")
      (footprint "MX_SW-4")
      (description "with Fixation pins  1-Pole")
      (libsource (lib "KeyBoard") (part "MX_SW-4"))
    )
    (comp (ref "SW59")
      (value "MX_SW")
      (footprint "MX_SW-4")
      (description "with Fixation pins  1-Pole")
      (libsource (lib "KeyBoard") (part "MX_SW-4"))
    )
    (comp (ref "SW60")
      (value "MX_SW")
      (footprint "MX_SW-4")
      (description "with Fixation pins  1-Pole")
      (libsource (lib "KeyBoard") (part "MX_SW-4"))
    )
    (comp (ref "SW61")
      (value "MX_SW")
      (footprint "MX_SW-4")
      (description "with Fixation pins  1-Pole")
      (libsource (lib "KeyBoard") (part "MX_SW-4"))
    )
    (comp (ref "SW62")
      (value "MX_SW")
      (footprint "MX_SW-4")
      (description "with Fixation pins  1-Pole")
      (libsource (lib "KeyBoard") (part "MX_SW-4"))
    )
    (comp (ref "SW63")
      (value "MX_SW")
      (footprint "MX_SW-4")
      (description "with Fixation pins  1-Pole")
      (libsource (lib "KeyBoard") (part "MX_SW-4"))
    )
    (comp (ref "SW64")
      (value "MX_SW")
      (footprint "MX_SW-4")
      (description "with Fixation pins  1-Pole")
      (libsource (lib "KeyBoard") (part "MX_SW-4"))
    )
    (comp (ref "SW65")
      (value "MX_SW")
      (footprint "MX_SW-4")
      (description "with Fixation pins  1-Pole")
      (libsource (lib "KeyBoard") (part "MX_SW-4"))
    )
    (comp (ref "SW66")
      (value "MX_SW")
      (footprint "MX_SW-4")
      (description "with Fixation pins  1-Pole")
      (libsource (lib "KeyBoard") (part "MX_SW-4"))
    )
    (comp (ref "SW67")
      (value "MX_SW")
      (footprint "MX_SW-4")
      (description "with Fixation pins  1-Pole")
      (libsource (lib "KeyBoard") (part "MX_SW-4"))
    )
    (comp (ref "SW68")
      (value "MX_SW")
      (footprint "MX_SW-4")
      (description "with Fixation pins  1-Pole")
      (libsource (lib "KeyBoard") (part "MX_SW-4"))
    )
    (comp (ref "SW69")
      (value "MX_SW")
      (footprint "MX_SW-4")
      (description "with Fixation pins  1-Pole")
      (libsource (lib "KeyBoard") (part "MX_SW-4"))
    )
    (comp (ref "SW70")
      (value "MX_SW")
      (footprint "MX_SW-4")
      (description "with Fixation pins  1-Pole")
      (libsource (lib "KeyBoard") (part "MX_SW-4"))
    )
    (comp (ref "SW71")
      (value "MX_SW")
      (footprint "MX_SW-4")
      (description "with Fixation pins  1-Pole")
      (libsource (lib "KeyBoard") (part "MX_SW-4"))
    )
    (comp (ref "SW72")
      (value "MX_SW")
      (footprint "MX_SW-4")
      (description "with Fixation pins  1-Pole")
      (libsource (lib "KeyBoard") (part "MX_SW-4"))
    )
    (comp (ref "SW73")
      (value "MX_SW")
      (footprint "MX_SW-4")
      (description "with Fixation pins  1-Pole")
      (libsource (lib "KeyBoard") (part "MX_SW-4"))
    )
    (comp (ref "SW74")
      (value "MX_SW")
      (footprint "MX_SW-4")
      (description "with Fixation pins  1-Pole")
      (libsource (lib "KeyBoard") (part "MX_SW-4"))
    )
    (comp (ref "SW75")
      (value "MX_SW")
      (footprint "MX_SW-4")
      (description "with Fixation pins  1-Pole")
      (libsource (lib "KeyBoard") (part "MX_SW-4"))
    )
    (comp (ref "SW76")
      (value "MX_SW")
      (footprint "MX_SW-4")
      (description "with Fixation pins  1-Pole")
      (libsource (lib "KeyBoard") (part "MX_SW-4"))
    )
    (comp (ref "SW77")
      (value "MX_SW")
      (footprint "MX_SW-4")
      (description "with Fixation pins  1-Pole")
      (libsource (lib "KeyBoard") (part "MX_SW-4"))
    )
    (comp (ref "SW78")
      (value "MX_SW")
      (footprint "MX_SW-4")
      (description "with Fixation pins  1-Pole")
      (libsource (lib "KeyBoard") (part "MX_SW-4"))
    )
    (comp (ref "SW79")
      (value "MX_SW")
      (footprint "MX_SW-4")
      (description "with Fixation pins  1-Pole")
      (libsource (lib "KeyBoard") (part "MX_SW-4"))
    )
    (comp (ref "SW80")
      (value "MX_SW")
      (footprint "MX_SW-4")
      (description "with Fixation pins  1-Pole")
      (libsource (lib "KeyBoard") (part "MX_SW-4"))
    )
    (comp (ref "SW81")
      (value "MX_SW")
      (footprint "MX_SW-4")
      (description "with Fixation pins  1-Pole")
      (libsource (lib "KeyBoard") (part "MX_SW-4"))
    )
    (comp (ref "SW82")
      (value "MX_SW")
      (footprint "MX_SW-4")
      (description "with Fixation pins  1-Pole")
      (libsource (lib "KeyBoard") (part "MX_SW-4"))
    )
    (comp (ref "SW83")
      (value "MX_SW")
      (footprint "MX_SW-4")
      (description "with Fixation pins  1-Pole")
      (libsource (lib "KeyBoard") (part "MX_SW-4"))
    )
    (comp (ref "SW84")
      (value "MX_SW")
      (footprint "MX_SW-4")
      (description "with Fixation pins  1-Pole")
      (libsource (lib "KeyBoard") (part "MX_SW-4"))
    )
    (comp (ref "SW85")
      (value "MX_SW")
      (footprint "MX_SW-4")
      (description "with Fixation pins  1-Pole")
      (libsource (lib "KeyBoard") (part "MX_SW-4"))
    )
    (comp (ref "SW86")
      (value "MX_SW")
      (footprint "MX_SW-4")
      (description "with Fixation pins  1-Pole")
      (libsource (lib "KeyBoard") (part "MX_SW-4"))
    )
    (comp (ref "SW87")
      (value "MX_SW")
      (footprint "MX_SW-4")
      (description "with Fixation pins  1-Pole")
      (libsource (lib "KeyBoard") (part "MX_SW-4"))
    )
    (comp (ref "SW88")
      (value "MX_SW")
      (footprint "MX_SW-4")
      (description "with Fixation pins  1-Pole")
      (libsource (lib "KeyBoard") (part "MX_SW-4"))
    )
    (comp (ref "SW89")
      (value "MX_SW")
      (footprint "MX_SW-4")
      (description "with Fixation pins  1-Pole")
      (libsource (lib "KeyBoard") (part "MX_SW-4"))
    )
    (comp (ref "SW90")
      (value "MX_SW")
      (footprint "MX_SW-4")
      (description "with Fixation pins  1-Pole")
      (libsource (lib "KeyBoard") (part "MX_SW-4"))
    )
    (comp (ref "SW91")
      (value "MX_SW")
      (footprint "MX_SW-4")
      (description "with Fixation pins  1-Pole")
      (libsource (lib "KeyBoard") (part "MX_SW-4"))
    )
    (comp (ref "SW92")
      (value "MX_SW")
      (footprint "MX_SW-4")
      (description "with Fixation pins  1-Pole")
      (libsource (lib "KeyBoard") (part "MX_SW-4"))
    )
    (comp (ref "SW93")
      (value "MX_SW")
      (footprint "MX_SW-4")
      (description "with Fixation pins  1-Pole")
      (libsource (lib "KeyBoard") (part "MX_SW-4"))
    )
    (comp (ref "SW94")
      (value "MX_SW")
      (footprint "MX_SW-4")
      (description "with Fixation pins  1-Pole")
      (libsource (lib "KeyBoard") (part "MX_SW-4"))
    )
    (comp (ref "SW95")
      (value "MX_SW")
      (footprint "MX_SW-4")
      (description "with Fixation pins  1-Pole")
      (libsource (lib "KeyBoard") (part "MX_SW-4"))
    )
    (comp (ref "SW96")
      (value "MX_SW")
      (footprint "MX_SW-4")
      (description "with Fixation pins  1-Pole")
      (libsource (lib "KeyBoard") (part "MX_SW-4"))
    )
    (comp (ref "SW97")
      (value "MX_SW")
      (footprint "MX_SW-4")
      (description "with Fixation pins  1-Pole")
      (libsource (lib "KeyBoard") (part "MX_SW-4"))
    )
    (comp (ref "SW98")
      (value "MX_SW")
      (footprint "MX_SW-4")
      (description "with Fixation pins  1-Pole")
      (libsource (lib "KeyBoard") (part "MX_SW-4"))
    )
    (comp (ref "SW99")
      (value "MX_SW")
      (footprint "MX_SW-4")
      (description "with Fixation pins  1-Pole")
      (libsource (lib "KeyBoard") (part "MX_SW-4"))
    )
    (comp (ref "SW100")
      (value "MX_SW")
      (footprint "MX_SW-4")
      (description "with Fixation pins  1-Pole")
      (libsource (lib "KeyBoard") (part "MX_SW-4"))
    )
    (comp (ref "SW101")
      (value "MX_SW")
      (footprint "MX_SW-4")
      (description "with Fixation pins  1-Pole")
      (libsource (lib "KeyBoard") (part "MX_SW-4"))
    )
    (comp (ref "SW102")
      (value "MX_SW")
      (footprint "MX_SW-4")
      (description "with Fixation pins  1-Pole")
      (libsource (lib "KeyBoard") (part "MX_SW-4"))
    )
    (comp (ref "SW103")
      (value "MX_SW")
      (footprint "MX_SW-4")
      (description "with Fixation pins  1-Pole")
      (libsource (lib "KeyBoard") (part "MX_SW-4"))
    )
    (comp (ref "SW104")
      (value "MX_SW")
      (footprint "MX_SW-4")
      (description "with Fixation pins  1-Pole")
      (libsource (lib "KeyBoard") (part "MX_SW-4"))
    )
    (comp (ref "U1")
      (value "STC15W4K320S4")
      (footprint "LQFP:LQFP44 10X10_M")
      (description "IC芯片")
      (libsource (lib "KeyBoard") (part "STC15F2K60S2"))
    )
    (comp (ref "U2")
      (value "STC15F100W")
      (footprint "SOIC-8")
      (libsource (lib "KeyBoard") (part "STC15F100W"))
    )
    (comp (ref "U3") (value "CH9329") (footprint "SOP16") (libsource (lib "KeyBoard") (part "CH9329")))
    (comp (ref "U4") (value "USB-A") (footprint "usb a") (libsource (lib "KeyBoard") (part "USB-MICRO")))
    (comp (ref "U5")
      (value "ams1117")
      (footprint "SOT223_N")
      (description "AMS1117")
      (libsource (lib "KeyBoard") (part "ams1117"))
    )
    (comp (ref "U7") (value "USB-TTL") (footprint "4pin排针") (libsource (lib "KeyBoard") (part "BLUETOOTH")))
    (comp (ref "U8") (value "USB-TTL") (footprint "4pin排针") (libsource (lib "KeyBoard") (part "BLUETOOTH")))
    (comp (ref "U9") (value "MH-CD42") (footprint "MH-CD42") (libsource (lib "KeyBoard") (part "MH-CD42")))
  )
  (nets
    (net (code "1") (name "/3.3V") (class "Default")
      (node (ref "C9") (pin "1") (pinfunction "1_1") (pintype "passive"))
      (node (ref "R1") (pin "12") (pinfunction "VCC_12") (pintype "passive"))
      (node (ref "U5") (pin "2") (pinfunction "VOUT_2") (pintype "passive"))
    )
    (net (code "2") (name "/D1") (class "Default")
      (node (ref "*86") (pin "4") (pinfunction "DOUT_4") (pintype "passive"))
      (node (ref "*87") (pin "2") (pinfunction "DIN_2") (pintype "passive"))
    )
    (net (code "3") (name "/D2") (class "Default")
      (node (ref "*68") (pin "4") (pinfunction "DOUT_4") (pintype "passive"))
      (node (ref "*69") (pin "2") (pinfunction "DIN_2") (pintype "passive"))
    )
    (net (code "4") (name "/D3") (class "Default")
      (node (ref "*51") (pin "4") (pinfunction "DOUT_4") (pintype "passive"))
      (node (ref "*52") (pin "2") (pinfunction "DIN_2") (pintype "passive"))
    )
    (net (code "5") (name "/D4") (class "Default")
      (node (ref "*34") (pin "4") (pinfunction "DOUT_4") (pintype "passive"))
      (node (ref "*35") (pin "2") (pinfunction "DIN_2") (pintype "passive"))
    )
    (net (code "6") (name "/D5") (class "Default")
      (node (ref "*16") (pin "4") (pinfunction "DOUT_4") (pintype "passive"))
      (node (ref "*17") (pin "2") (pinfunction "DIN_2") (pintype "passive"))
    )
    (net (code "7") (name "/P0.0") (class "Default")
      (node (ref "SW17") (pin "2") (pinfunction "1_2") (pintype "passive"))
      (node (ref "SW18") (pin "2") (pinfunction "1_2") (pintype "passive"))
      (node (ref "SW19") (pin "2") (pinfunction "1_2") (pintype "passive"))
      (node (ref "SW20") (pin "2") (pinfunction "1_2") (pintype "passive"))
      (node (ref "SW21") (pin "2") (pinfunction "1_2") (pintype "passive"))
      (node (ref "SW22") (pin "2") (pinfunction "1_2") (pintype "passive"))
      (node (ref "SW23") (pin "2") (pinfunction "1_2") (pintype "passive"))
      (node (ref "SW24") (pin "2") (pinfunction "1_2") (pintype "passive"))
      (node (ref "SW25") (pin "2") (pinfunction "1_2") (pintype "passive"))
      (node (ref "SW26") (pin "2") (pinfunction "1_2") (pintype "passive"))
      (node (ref "SW27") (pin "2") (pinfunction "1_2") (pintype "passive"))
      (node (ref "SW28") (pin "2") (pinfunction "1_2") (pintype "passive"))
      (node (ref "SW29") (pin "2") (pinfunction "1_2") (pintype "passive"))
      (node (ref "SW30") (pin "2") (pinfunction "1_2") (pintype "passive"))
      (node (ref "SW31") (pin "2") (pinfunction "1_2") (pintype "passive"))
      (node (ref "SW32") (pin "2") (pinfunction "1_2") (pintype "passive"))
      (node (ref "SW33") (pin "2") (pinfunction "1_2") (pintype "passive"))
      (node (ref "SW34") (pin "2") (pinfunction "1_2") (pintype "passive"))
      (node (ref "U1") (pin "40") (pinfunction "P0.0_40") (pintype "passive"))
    )
    (net (code "8") (name "/P0.1") (class "Default")
      (node (ref "SW35") (pin "2") (pinfunction "1_2") (pintype "passive"))
      (node (ref "SW36") (pin "2") (pinfunction "1_2") (pintype "passive"))
      (node (ref "SW37") (pin "2") (pinfunction "1_2") (pintype "passive"))
      (node (ref "SW38") (pin "2") (pinfunction "1_2") (pintype "passive"))
      (node (ref "SW39") (pin "2") (pinfunction "1_2") (pintype "passive"))
      (node (ref "SW40") (pin "2") (pinfunction "1_2") (pintype "passive"))
      (node (ref "SW41") (pin "2") (pinfunction "1_2") (pintype "passive"))
      (node (ref "SW42") (pin "2") (pinfunction "1_2") (pintype "passive"))
      (node (ref "SW43") (pin "2") (pinfunction "1_2") (pintype "passive"))
      (node (ref "SW44") (pin "2") (pinfunction "1_2") (pintype "passive"))
      (node (ref "SW45") (pin "2") (pinfunction "1_2") (pintype "passive"))
      (node (ref "SW46") (pin "2") (pinfunction "1_2") (pintype "passive"))
      (node (ref "SW47") (pin "2") (pinfunction "1_2") (pintype "passive"))
      (node (ref "SW48") (pin "2") (pinfunction "1_2") (pintype "passive"))
      (node (ref "SW49") (pin "2") (pinfunction "1_2") (pintype "passive"))
      (node (ref "SW50") (pin "2") (pinfunction "1_2") (pintype "passive"))
      (node (ref "SW51") (pin "2") (pinfunction "1_2") (pintype "passive"))
      (node (ref "U1") (pin "41") (pinfunction "P0.1_41") (pintype "passive"))
    )
    (net (code "9") (name "/P0.4") (class "Default")
      (node (ref "SW52") (pin "2") (pinfunction "1_2") (pintype "passive"))
      (node (ref "SW53") (pin "2") (pinfunction "1_2") (pintype "passive"))
      (node (ref "SW54") (pin "2") (pinfunction "1_2") (pintype "passive"))
      (node (ref "SW55") (pin "2") (pinfunction "1_2") (pintype "passive"))
      (node (ref "SW56") (pin "2") (pinfunction "1_2") (pintype "passive"))
      (node (ref "SW57") (pin "2") (pinfunction "1_2") (pintype "passive"))
      (node (ref "SW58") (pin "2") (pinfunction "1_2") (pintype "passive"))
      (node (ref "SW59") (pin "2") (pinfunction "1_2") (pintype "passive"))
      (node (ref "SW60") (pin "2") (pinfunction "1_2") (pintype "passive"))
      (node (ref "SW61") (pin "2") (pinfunction "1_2") (pintype "passive"))
      (node (ref "SW62") (pin "2") (pinfunction "1_2") (pintype "passive"))
      (node (ref "SW63") (pin "2") (pinfunction "1_2") (pintype "passive"))
      (node (ref "SW64") (pin "2") (pinfunction "1_2") (pintype "passive"))
      (node (ref "SW65") (pin "2") (pinfunction "1_2") (pintype "passive"))
      (node (ref "SW66") (pin "2") (pinfunction "1_2") (pintype "passive"))
      (node (ref "SW67") (pin "2") (pinfunction "1_2") (pintype "passive"))
      (node (ref "SW68") (pin "2") (pinfunction "1_2") (pintype "passive"))
      (node (ref "U1") (pin "44") (pinfunction "P0.4_44") (pintype "passive"))
    )
    (net (code "10") (name "/P0.5") (class "Default")
      (node (ref "SW69") (pin "2") (pinfunction "1_2") (pintype "passive"))
      (node (ref "SW70") (pin "2") (pinfunction "1_2") (pintype "passive"))
      (node (ref "SW71") (pin "2") (pinfunction "1_2") (pintype "passive"))
      (node (ref "SW72") (pin "2") (pinfunction "1_2") (pintype "passive"))
      (node (ref "SW73") (pin "2") (pinfunction "1_2") (pintype "passive"))
      (node (ref "SW74") (pin "2") (pinfunction "1_2") (pintype "passive"))
      (node (ref "SW75") (pin "2") (pinfunction "1_2") (pintype "passive"))
      (node (ref "SW76") (pin "2") (pinfunction "1_2") (pintype "passive"))
      (node (ref "SW77") (pin "2") (pinfunction "1_2") (pintype "passive"))
      (node (ref "SW78") (pin "2") (pinfunction "1_2") (pintype "passive"))
      (node (ref "SW79") (pin "2") (pinfunction "1_2") (pintype "passive"))
      (node (ref "SW80") (pin "2") (pinfunction "1_2") (pintype "passive"))
      (node (ref "SW81") (pin "2") (pinfunction "1_2") (pintype "passive"))
      (node (ref "SW82") (pin "2") (pinfunction "1_2") (pintype "passive"))
      (node (ref "SW83") (pin "2") (pinfunction "1_2") (pintype "passive"))
      (node (ref "SW84") (pin "2") (pinfunction "1_2") (pintype "passive"))
      (node (ref "SW85") (pin "2") (pinfunction "1_2") (pintype "passive"))
      (node (ref "SW86") (pin "2") (pinfunction "1_2") (pintype "passive"))
      (node (ref "U1") (pin "1") (pinfunction "P0.5_1") (pintype "passive"))
    )
    (net (code "11") (name "/P0.6") (class "Default")
      (node (ref "SW100") (pin "2") (pinfunction "1_2") (pintype "passive"))
      (node (ref "SW101") (pin "2") (pinfunction "1_2") (pintype "passive"))
      (node (ref "SW102") (pin "2") (pinfunction "1_2") (pintype "passive"))
      (node (ref "SW103") (pin "2") (pinfunction "1_2") (pintype "passive"))
      (node (ref "SW104") (pin "2") (pinfunction "1_2") (pintype "passive"))
      (node (ref "SW87") (pin "2") (pinfunction "1_2") (pintype "passive"))
      (node (ref "SW88") (pin "2") (pinfunction "1_2") (pintype "passive"))
      (node (ref "SW89") (pin "2") (pinfunction "1_2") (pintype "passive"))
      (node (ref "SW90") (pin "2") (pinfunction "1_2") (pintype "passive"))
      (node (ref "SW91") (pin "2") (pinfunction "1_2") (pintype "passive"))
      (node (ref "SW92") (pin "2") (pinfunction "1_2") (pintype "passive"))
      (node (ref "SW93") (pin "2") (pinfunction "1_2") (pintype "passive"))
      (node (ref "SW94") (pin "2") (pinfunction "1_2") (pintype "passive"))
      (node (ref "SW95") (pin "2") (pinfunction "1_2") (pintype "passive"))
      (node (ref "SW96") (pin "2") (pinfunction "1_2") (pintype "passive"))
      (node (ref "SW97") (pin "2") (pinfunction "1_2") (pintype "passive"))
      (node (ref "SW98") (pin "2") (pinfunction "1_2") (pintype "passive"))
      (node (ref "SW99") (pin "2") (pinfunction "1_2") (pintype "passive"))
      (node (ref "U1") (pin "2") (pinfunction "P0.6_2") (pintype "passive"))
    )
    (net (code "12") (name "/P2.0") (class "Default")
      (node (ref "D12") (pin "2") (pinfunction "2_2") (pintype "passive"))
      (node (ref "D28") (pin "2") (pinfunction "2_2") (pintype "passive"))
      (node (ref "D46") (pin "2") (pinfunction "2_2") (pintype "passive"))
      (node (ref "D63") (pin "2") (pinfunction "2_2") (pintype "passive"))
      (node (ref "D80") (pin "2") (pinfunction "2_2") (pintype "passive"))
      (node (ref "D98") (pin "2") (pinfunction "2_2") (pintype "passive"))
      (node (ref "U1") (pin "30") (pinfunction "P2.0/RSTOUT_LOW_30") (pintype "passive"))
    )
    (net (code "13") (name "/P2.1") (class "Default")
      (node (ref "D11") (pin "2") (pinfunction "2_2") (pintype "passive"))
      (node (ref "D27") (pin "2") (pinfunction "2_2") (pintype "passive"))
      (node (ref "D45") (pin "2") (pinfunction "2_2") (pintype "passive"))
      (node (ref "D62") (pin "2") (pinfunction "2_2") (pintype "passive"))
      (node (ref "D79") (pin "2") (pinfunction "2_2") (pintype "passive"))
      (node (ref "D97") (pin "2") (pinfunction "2_2") (pintype "passive"))
      (node (ref "U1") (pin "31") (pinfunction "P2.1_31") (pintype "passive"))
    )
    (net (code "14") (name "/P2.2") (class "Default")
      (node (ref "D10") (pin "2") (pinfunction "2_2") (pintype "passive"))
      (node (ref "D26") (pin "2") (pinfunction "2_2") (pintype "passive"))
      (node (ref "D44") (pin "2") (pinfunction "2_2") (pintype "passive"))
      (node (ref "D61") (pin "2") (pinfunction "2_2") (pintype "passive"))
      (node (ref "D78") (pin "2") (pinfunction "2_2") (pintype "passive"))
      (node (ref "D96") (pin "2") (pinfunction "2_2") (pintype "passive"))
      (node (ref "U1") (pin "32") (pinfunction "P2.2_32") (pintype "passive"))
    )
    (net (code "15") (name "/P2.3") (class "Default")
      (node (ref "D25") (pin "2") (pinfunction "2_2") (pintype "passive"))
      (node (ref "D43") (pin "2") (pinfunction "2_2") (pintype "passive"))
      (node (ref "D60") (pin "2") (pinfunction "2_2") (pintype "passive"))
      (node (ref "D77") (pin "2") (pinfunction "2_2") (pintype "passive"))
      (node (ref "D9") (pin "2") (pinfunction "2_2") (pintype "passive"))
      (node (ref "D95") (pin "2") (pinfunction "2_2") (pintype "passive"))
      (node (ref "U1") (pin "33") (pinfunction "P2.3_33") (pintype "passive"))
    )
    (net (code "16") (name "/P2.4") (class "Default")
      (node (ref "D24") (pin "2") (pinfunction "2_2") (pintype "passive"))
      (node (ref "D42") (pin "2") (pinfunction "2_2") (pintype "passive"))
      (node (ref "D59") (pin "2") (pinfunction "2_2") (pintype "passive"))
      (node (ref "D76") (pin "2") (pinfunction "2_2") (pintype "passive"))
      (node (ref "D8") (pin "2") (pinfunction "2_2") (pintype "passive"))
      (node (ref "D94") (pin "2") (pinfunction "2_2") (pintype "passive"))
      (node (ref "U1") (pin "34") (pinfunction "P2.4_34") (pintype "passive"))
    )
    (net (code "17") (name "/P2.5") (class "Default")
      (node (ref "D23") (pin "2") (pinfunction "2_2") (pintype "passive"))
      (node (ref "D41") (pin "2") (pinfunction "2_2") (pintype "passive"))
      (node (ref "D58") (pin "2") (pinfunction "2_2") (pintype "passive"))
      (node (ref "D7") (pin "2") (pinfunction "2_2") (pintype "passive"))
      (node (ref "D75") (pin "2") (pinfunction "2_2") (pintype "passive"))
      (node (ref "D93") (pin "2") (pinfunction "2_2") (pintype "passive"))
      (node (ref "U1") (pin "35") (pinfunction "P2.5_35") (pintype "passive"))
    )
    (net (code "18") (name "/P2.6") (class "Default")
      (node (ref "D22") (pin "2") (pinfunction "2_2") (pintype "passive"))
      (node (ref "D40") (pin "2") (pinfunction "2_2") (pintype "passive"))
      (node (ref "D57") (pin "2") (pinfunction "2_2") (pintype "passive"))
      (node (ref "D6") (pin "2") (pinfunction "2_2") (pintype "passive"))
      (node (ref "D74") (pin "2") (pinfunction "2_2") (pintype "passive"))
      (node (ref "D92") (pin "2") (pinfunction "2_2") (pintype "passive"))
      (node (ref "U1") (pin "36") (pinfunction "P2.6_36") (pintype "passive"))
    )
    (net (code "19") (name "/P2.7") (class "Default")
      (node (ref "D21") (pin "2") (pinfunction "2_2") (pintype "passive"))
      (node (ref "D39") (pin "2") (pinfunction "2_2") (pintype "passive"))
      (node (ref "D5") (pin "2") (pinfunction "2_2") (pintype "passive"))
      (node (ref "D56") (pin "2") (pinfunction "2_2") (pintype "passive"))
      (node (ref "D73") (pin "2") (pinfunction "2_2") (pintype "passive"))
      (node (ref "D91") (pin "2") (pinfunction "2_2") (pintype "passive"))
      (node (ref "U1") (pin "37") (pinfunction "P2.7_37") (pintype "passive"))
    )
    (net (code "20") (name "/P3.2") (class "Default")
      (node (ref "*104") (pin "4") (pinfunction "DOUT_4") (pintype "passive"))
      (node (ref "U2") (pin "7") (pinfunction "P3.2_7") (pintype "passive"))
    )
    (net (code "21") (name "/P3.3") (class "Default")
      (node (ref "D107") (pin "2") (pinfunction "2_2") (pintype "passive"))
      (node (ref "D37") (pin "2") (pinfunction "2_2") (pintype "passive"))
      (node (ref "D89") (pin "2") (pinfunction "2_2") (pintype "passive"))
      (node (ref "U1") (pin "21") (pinfunction "P3.3/INT1_21") (pintype "passive"))
    )
    (net (code "22") (name "/P3.4") (class "Default")
      (node (ref "D106") (pin "2") (pinfunction "2_2") (pintype "passive"))
      (node (ref "D36") (pin "2") (pinfunction "2_2") (pintype "passive"))
      (node (ref "D54") (pin "2") (pinfunction "2_2") (pintype "passive"))
      (node (ref "D71") (pin "2") (pinfunction "2_2") (pintype "passive"))
      (node (ref "D88") (pin "2") (pinfunction "2_2") (pintype "passive"))
      (node (ref "U1") (pin "22") (pinfunction "P3.4/T0/T1CLKO/ECI_2_22") (pintype "passive"))
    )
    (net (code "23") (name "/P3.5") (class "Default")
      (node (ref "D105") (pin "2") (pinfunction "2_2") (pintype "passive"))
      (node (ref "D19") (pin "2") (pinfunction "2_2") (pintype "passive"))
      (node (ref "D35") (pin "2") (pinfunction "2_2") (pintype "passive"))
      (node (ref "D53") (pin "2") (pinfunction "2_2") (pintype "passive"))
      (node (ref "D70") (pin "2") (pinfunction "2_2") (pintype "passive"))
      (node (ref "D87") (pin "2") (pinfunction "2_2") (pintype "passive"))
      (node (ref "U1") (pin "23") (pinfunction "P3.5_23") (pintype "passive"))
    )
    (net (code "24") (name "/P3.6") (class "Default")
      (node (ref "D104") (pin "2") (pinfunction "2_2") (pintype "passive"))
      (node (ref "D18") (pin "2") (pinfunction "2_2") (pintype "passive"))
      (node (ref "D34") (pin "2") (pinfunction "2_2") (pintype "passive"))
      (node (ref "D52") (pin "2") (pinfunction "2_2") (pintype "passive"))
      (node (ref "D69") (pin "2") (pinfunction "2_2") (pintype "passive"))
      (node (ref "D86") (pin "2") (pinfunction "2_2") (pintype "passive"))
      (node (ref "U1") (pin "24") (pinfunction "P3.6/~{INT2}/RxD_2_24") (pintype "passive"))
    )
    (net (code "25") (name "/P3.7") (class "Default")
      (node (ref "D103") (pin "2") (pinfunction "2_2") (pintype "passive"))
      (node (ref "D17") (pin "2") (pinfunction "2_2") (pintype "passive"))
      (node (ref "D33") (pin "2") (pinfunction "2_2") (pintype "passive"))
      (node (ref "D51") (pin "2") (pinfunction "2_2") (pintype "passive"))
      (node (ref "D68") (pin "2") (pinfunction "2_2") (pintype "passive"))
      (node (ref "D85") (pin "2") (pinfunction "2_2") (pintype "passive"))
      (node (ref "U1") (pin "25") (pinfunction "P3.7/~{INT3}/TxD_2_25") (pintype "passive"))
    )
    (net (code "26") (name "/P4.1") (class "Default")
      (node (ref "D102") (pin "2") (pinfunction "2_2") (pintype "passive"))
      (node (ref "D16") (pin "2") (pinfunction "2_2") (pintype "passive"))
      (node (ref "D32") (pin "2") (pinfunction "2_2") (pintype "passive"))
      (node (ref "D50") (pin "2") (pinfunction "2_2") (pintype "passive"))
      (node (ref "D67") (pin "2") (pinfunction "2_2") (pintype "passive"))
      (node (ref "D84") (pin "2") (pinfunction "2_2") (pintype "passive"))
      (node (ref "U1") (pin "26") (pinfunction "P4.1_26") (pintype "passive"))
    )
    (net (code "27") (name "/P4.2") (class "Default")
      (node (ref "D101") (pin "2") (pinfunction "2_2") (pintype "passive"))
      (node (ref "D15") (pin "2") (pinfunction "2_2") (pintype "passive"))
      (node (ref "D31") (pin "2") (pinfunction "2_2") (pintype "passive"))
      (node (ref "D49") (pin "2") (pinfunction "2_2") (pintype "passive"))
      (node (ref "D66") (pin "2") (pinfunction "2_2") (pintype "passive"))
      (node (ref "D83") (pin "2") (pinfunction "2_2") (pintype "passive"))
      (node (ref "U1") (pin "27") (pinfunction "P4.2_27") (pintype "passive"))
    )
    (net (code "28") (name "/P4.3") (class "Default")
      (node (ref "D100") (pin "2") (pinfunction "2_2") (pintype "passive"))
      (node (ref "D14") (pin "2") (pinfunction "2_2") (pintype "passive"))
      (node (ref "D30") (pin "2") (pinfunction "2_2") (pintype "passive"))
      (node (ref "D48") (pin "2") (pinfunction "2_2") (pintype "passive"))
      (node (ref "D65") (pin "2") (pinfunction "2_2") (pintype "passive"))
      (node (ref "D82") (pin "2") (pinfunction "2_2") (pintype "passive"))
      (node (ref "U1") (pin "28") (pinfunction "P4.3_28") (pintype "passive"))
    )
    (net (code "29") (name "/P4.4") (class "Default")
      (node (ref "D13") (pin "2") (pinfunction "2_2") (pintype "passive"))
      (node (ref "D29") (pin "2") (pinfunction "2_2") (pintype "passive"))
      (node (ref "D47") (pin "2") (pinfunction "2_2") (pintype "passive"))
      (node (ref "D64") (pin "2") (pinfunction "2_2") (pintype "passive"))
      (node (ref "D81") (pin "2") (pinfunction "2_2") (pintype "passive"))
      (node (ref "D99") (pin "2") (pinfunction "2_2") (pintype "passive"))
      (node (ref "U1") (pin "29") (pinfunction "P4.4_29") (pintype "passive"))
    )
    (net (code "30") (name "/P4.5") (class "Default")
      (node (ref "D20") (pin "2") (pinfunction "2_2") (pintype "passive"))
      (node (ref "D38") (pin "2") (pinfunction "2_2") (pintype "passive"))
      (node (ref "D4") (pin "2") (pinfunction "2_2") (pintype "passive"))
      (node (ref "D55") (pin "2") (pinfunction "2_2") (pintype "passive"))
      (node (ref "D72") (pin "2") (pinfunction "2_2") (pintype "passive"))
      (node (ref "D90") (pin "2") (pinfunction "2_2") (pintype "passive"))
      (node (ref "U1") (pin "38") (pinfunction "P4.5_38") (pintype "passive"))
    )
    (net (code "31") (name "/P4.6") (class "Default")
      (node (ref "SW1") (pin "2") (pinfunction "1_2") (pintype "passive"))
      (node (ref "SW10") (pin "2") (pinfunction "1_2") (pintype "passive"))
      (node (ref "SW11") (pin "2") (pinfunction "1_2") (pintype "passive"))
      (node (ref "SW12") (pin "2") (pinfunction "1_2") (pintype "passive"))
      (node (ref "SW13") (pin "2") (pinfunction "1_2") (pintype "passive"))
      (node (ref "SW14") (pin "2") (pinfunction "1_2") (pintype "passive"))
      (node (ref "SW15") (pin "2") (pinfunction "1_2") (pintype "passive"))
      (node (ref "SW16") (pin "2") (pinfunction "1_2") (pintype "passive"))
      (node (ref "SW2") (pin "2") (pinfunction "1_2") (pintype "passive"))
      (node (ref "SW3") (pin "2") (pinfunction "1_2") (pintype "passive"))
      (node (ref "SW4") (pin "2") (pinfunction "1_2") (pintype "passive"))
      (node (ref "SW5") (pin "2") (pinfunction "1_2") (pintype "passive"))
      (node (ref "SW6") (pin "2") (pinfunction "1_2") (pintype "passive"))
      (node (ref "SW7") (pin "2") (pinfunction "1_2") (pintype "passive"))
      (node (ref "SW8") (pin "2") (pinfunction "1_2") (pintype "passive"))
      (node (ref "SW9") (pin "2") (pinfunction "1_2") (pintype "passive"))
      (node (ref "U1") (pin "39") (pinfunction "P4.6_39") (pintype "passive"))
    )
    (net (code "32") (name "/PD") (class "Default")
      (node (ref "*1") (pin "2") (pinfunction "DIN_2") (pintype "passive"))
      (node (ref "U2") (pin "8") (pinfunction "P3.3_8") (pintype "passive"))
    )
    (net (code "33") (name "/VDD") (class "Default")
      (node (ref "U4") (pin "1") (pinfunction "VBUS_1") (pintype "passive"))
      (node (ref "U9") (pin "6") (pinfunction "vin_6") (pintype "passive"))
    )
    (net (code "34") (name "/cr1") (class "Default")
      (node (ref "R1") (pin "2") (pinfunction "RXD_DD_2") (pintype "passive"))
      (node (ref "U1") (pin "19") (pinfunction "P3.1/TxD/T2_19") (pintype "passive"))
      (node (ref "U3") (pin "8") (pinfunction "RXD_8") (pintype "passive"))
      (node (ref "U7") (pin "3") (pinfunction "RXD_3") (pintype "passive"))
    )
    (net (code "35") (name "/cr2") (class "Default")
      (node (ref "R1") (pin "1") (pinfunction "TXD_DC_1") (pintype "passive"))
      (node (ref "U1") (pin "18") (pinfunction "P3.0/RxD/~{INT4}_18") (pintype "passive"))
      (node (ref "U3") (pin "7") (pinfunction "TXD_7") (pintype "passive"))
      (node (ref "U7") (pin "2") (pinfunction "TXD_2") (pintype "passive"))
    )
    (net (code "36") (name "/gnd0") (class "Default")
      (node (ref "U4") (pin "4") (pinfunction "GND_4") (pintype "passive"))
      (node (ref "U9") (pin "5") (pinfunction "gnd_5") (pintype "passive"))
    )
    (net (code "37") (name "GND") (class "Default")
      (node (ref "*1") (pin "3") (pinfunction "GND_3") (pintype "passive"))
      (node (ref "*10") (pin "3") (pinfunction "GND_3") (pintype "passive"))
      (node (ref "*100") (pin "3") (pinfunction "GND_3") (pintype "passive"))
      (node (ref "*101") (pin "3") (pinfunction "GND_3") (pintype "passive"))
      (node (ref "*102") (pin "3") (pinfunction "GND_3") (pintype "passive"))
      (node (ref "*103") (pin "3") (pinfunction "GND_3") (pintype "passive"))
      (node (ref "*104") (pin "3") (pinfunction "GND_3") (pintype "passive"))
      (node (ref "*11") (pin "3") (pinfunction "GND_3") (pintype "passive"))
      (node (ref "*12") (pin "3") (pinfunction "GND_3") (pintype "passive"))
      (node (ref "*13") (pin "3") (pinfunction "GND_3") (pintype "passive"))
      (node (ref "*14") (pin "3") (pinfunction "GND_3") (pintype "passive"))
      (node (ref "*15") (pin "3") (pinfunction "GND_3") (pintype "passive"))
      (node (ref "*16") (pin "3") (pinfunction "GND_3") (pintype "passive"))
      (node (ref "*17") (pin "3") (pinfunction "GND_3") (pintype "passive"))
      (node (ref "*18") (pin "3") (pinfunction "GND_3") (pintype "passive"))
      (node (ref "*19") (pin "3") (pinfunction "GND_3") (pintype "passive"))
      (node (ref "*2") (pin "3") (pinfunction "GND_3") (pintype "passive"))
      (node (ref "*20") (pin "3") (pinfunction "GND_3") (pintype "passive"))
      (node (ref "*21") (pin "3") (pinfunction "GND_3") (pintype "passive"))
      (node (ref "*22") (pin "3") (pinfunction "GND_3") (pintype "passive"))
      (node (ref "*23") (pin "3") (pinfunction "GND_3") (pintype "passive"))
      (node (ref "*24") (pin "3") (pinfunction "GND_3") (pintype "passive"))
      (node (ref "*25") (pin "3") (pinfunction "GND_3") (pintype "passive"))
      (node (ref "*26") (pin "3") (pinfunction "GND_3") (pintype "passive"))
      (node (ref "*27") (pin "3") (pinfunction "GND_3") (pintype "passive"))
      (node (ref "*28") (pin "3") (pinfunction "GND_3") (pintype "passive"))
      (node (ref "*29") (pin "3") (pinfunction "GND_3") (pintype "passive"))
      (node (ref "*3") (pin "3") (pinfunction "GND_3") (pintype "passive"))
      (node (ref "*30") (pin "3") (pinfunction "GND_3") (pintype "passive"))
      (node (ref "*31") (pin "3") (pinfunction "GND_3") (pintype "passive"))
      (node (ref "*32") (pin "3") (pinfunction "GND_3") (pintype "passive"))
      (node (ref "*33") (pin "3") (pinfunction "GND_3") (pintype "passive"))
      (node (ref "*34") (pin "3") (pinfunction "GND_3") (pintype "passive"))
      (node (ref "*35") (pin "3") (pinfunction "GND_3") (pintype "passive"))
      (node (ref "*36") (pin "3") (pinfunction "GND_3") (pintype "passive"))
      (node (ref "*37") (pin "3") (pinfunction "GND_3") (pintype "passive"))
      (node (ref "*38") (pin "3") (pinfunction "GND_3") (pintype "passive"))
      (node (ref "*39") (pin "3") (pinfunction "GND_3") (pintype "passive"))
      (node (ref "*4") (pin "3") (pinfunction "GND_3") (pintype "passive"))
      (node (ref "*40") (pin "3") (pinfunction "GND_3") (pintype "passive"))
      (node (ref "*41") (pin "3") (pinfunction "GND_3") (pintype "passive"))
      (node (ref "*42") (pin "3") (pinfunction "GND_3") (pintype "passive"))
      (node (ref "*43") (pin "3") (pinfunction "GND_3") (pintype "passive"))
      (node (ref "*44") (pin "3") (pinfunction "GND_3") (pintype "passive"))
      (node (ref "*45") (pin "3") (pinfunction "GND_3") (pintype "passive"))
      (node (ref "*46") (pin "3") (pinfunction "GND_3") (pintype "passive"))
      (node (ref "*47") (pin "3") (pinfunction "GND_3") (pintype "passive"))
      (node (ref "*48") (pin "3") (pinfunction "GND_3") (pintype "passive"))
      (node (ref "*49") (pin "3") (pinfunction "GND_3") (pintype "passive"))
      (node (ref "*5") (pin "3") (pinfunction "GND_3") (pintype "passive"))
      (node (ref "*50") (pin "3") (pinfunction "GND_3") (pintype "passive"))
      (node (ref "*51") (pin "3") (pinfunction "GND_3") (pintype "passive"))
      (node (ref "*52") (pin "3") (pinfunction "GND_3") (pintype "passive"))
      (node (ref "*53") (pin "3") (pinfunction "GND_3") (pintype "passive"))
      (node (ref "*54") (pin "3") (pinfunction "GND_3") (pintype "passive"))
      (node (ref "*55") (pin "3") (pinfunction "GND_3") (pintype "passive"))
      (node (ref "*56") (pin "3") (pinfunction "GND_3") (pintype "passive"))
      (node (ref "*57") (pin "3") (pinfunction "GND_3") (pintype "passive"))
      (node (ref "*58") (pin "3") (pinfunction "GND_3") (pintype "passive"))
      (node (ref "*59") (pin "3") (pinfunction "GND_3") (pintype "passive"))
      (node (ref "*6") (pin "3") (pinfunction "GND_3") (pintype "passive"))
      (node (ref "*60") (pin "3") (pinfunction "GND_3") (pintype "passive"))
      (node (ref "*61") (pin "3") (pinfunction "GND_3") (pintype "passive"))
      (node (ref "*62") (pin "3") (pinfunction "GND_3") (pintype "passive"))
      (node (ref "*63") (pin "3") (pinfunction "GND_3") (pintype "passive"))
      (node (ref "*64") (pin "3") (pinfunction "GND_3") (pintype "passive"))
      (node (ref "*65") (pin "3") (pinfunction "GND_3") (pintype "passive"))
      (node (ref "*66") (pin "3") (pinfunction "GND_3") (pintype "passive"))
      (node (ref "*67") (pin "3") (pinfunction "GND_3") (pintype "passive"))
      (node (ref "*68") (pin "3") (pinfunction "GND_3") (pintype "passive"))
      (node (ref "*69") (pin "3") (pinfunction "GND_3") (pintype "passive"))
      (node (ref "*7") (pin "3") (pinfunction "GND_3") (pintype "passive"))
      (node (ref "*70") (pin "3") (pinfunction "GND_3") (pintype "passive"))
      (node (ref "*71") (pin "3") (pinfunction "GND_3") (pintype "passive"))
      (node (ref "*72") (pin "3") (pinfunction "GND_3") (pintype "passive"))
      (node (ref "*73") (pin "3") (pinfunction "GND_3") (pintype "passive"))
      (node (ref "*74") (pin "3") (pinfunction "GND_3") (pintype "passive"))
      (node (ref "*75") (pin "3") (pinfunction "GND_3") (pintype "passive"))
      (node (ref "*76") (pin "3") (pinfunction "GND_3") (pintype "passive"))
      (node (ref "*77") (pin "3") (pinfunction "GND_3") (pintype "passive"))
      (node (ref "*78") (pin "3") (pinfunction "GND_3") (pintype "passive"))
      (node (ref "*79") (pin "3") (pinfunction "GND_3") (pintype "passive"))
      (node (ref "*8") (pin "3") (pinfunction "GND_3") (pintype "passive"))
      (node (ref "*80") (pin "3") (pinfunction "GND_3") (pintype "passive"))
      (node (ref "*81") (pin "3") (pinfunction "GND_3") (pintype "passive"))
      (node (ref "*82") (pin "3") (pinfunction "GND_3") (pintype "passive"))
      (node (ref "*83") (pin "3") (pinfunction "GND_3") (pintype "passive"))
      (node (ref "*84") (pin "3") (pinfunction "GND_3") (pintype "passive"))
      (node (ref "*85") (pin "3") (pinfunction "GND_3") (pintype "passive"))
      (node (ref "*86") (pin "3") (pinfunction "GND_3") (pintype "passive"))
      (node (ref "*87") (pin "3") (pinfunction "GND_3") (pintype "passive"))
      (node (ref "*88") (pin "3") (pinfunction "GND_3") (pintype "passive"))
      (node (ref "*89") (pin "3") (pinfunction "GND_3") (pintype "passive"))
      (node (ref "*9") (pin "3") (pinfunction "GND_3") (pintype "passive"))
      (node (ref "*90") (pin "3") (pinfunction "GND_3") (pintype "passive"))
      (node (ref "*91") (pin "3") (pinfunction "GND_3") (pintype "passive"))
      (node (ref "*92") (pin "3") (pinfunction "GND_3") (pintype "passive"))
      (node (ref "*93") (pin "3") (pinfunction "GND_3") (pintype "passive"))
      (node (ref "*94") (pin "3") (pinfunction "GND_3") (pintype "passive"))
      (node (ref "*95") (pin "3") (pinfunction "GND_3") (pintype "passive"))
      (node (ref "*96") (pin "3") (pinfunction "GND_3") (pintype "passive"))
      (node (ref "*97") (pin "3") (pinfunction "GND_3") (pintype "passive"))
      (node (ref "*98") (pin "3") (pinfunction "GND_3") (pintype "passive"))
      (node (ref "*99") (pin "3") (pinfunction "GND_3") (pintype "passive"))
      (node (ref "C1") (pin "1") (pinfunction "1_1") (pintype "passive"))
      (node (ref "C2") (pin "1") (pinfunction "1_1") (pintype "passive"))
      (node (ref "C3") (pin "1") (pinfunction "1_1") (pintype "passive"))
      (node (ref "C4") (pin "1") (pinfunction "1_1") (pintype "passive"))
      (node (ref "C5") (pin "1") (pinfunction "1_1") (pintype "passive"))
      (node (ref "C6") (pin "1") (pinfunction "1_1") (pintype "passive"))
      (node (ref "C7") (pin "1") (pinfunction "1_1") (pintype "passive"))
      (node (ref "C8") (pin "2") (pinfunction "2_2") (pintype "passive"))
      (node (ref "C9") (pin "2") (pinfunction "2_2") (pintype "passive"))
      (node (ref "R1") (pin "13") (pinfunction "GND_13") (pintype "passive"))
      (node (ref "U1") (pin "16") (pinfunction "GND_16") (pintype "passive"))
      (node (ref "U2") (pin "4") (pinfunction "GND_4") (pintype "passive"))
      (node (ref "U3") (pin "14") (pinfunction "GND_14") (pintype "passive"))
      (node (ref "U5") (pin "1") (pinfunction "GND_1") (pintype "passive"))
      (node (ref "U7") (pin "4") (pinfunction "GND_4") (pintype "passive"))
      (node (ref "U8") (pin "4") (pinfunction "GND_4") (pintype "passive"))
      (node (ref "U9") (pin "2") (pinfunction "gnd_2") (pintype "passive"))
    )
    (net (code "38") (name "Net-(*1-DOUT)") (class "Default")
      (node (ref "*1") (pin "4") (pinfunction "DOUT_4") (pintype "passive"))
      (node (ref "*2") (pin "2") (pinfunction "DIN_2") (pintype "passive"))
    )
    (net (code "39") (name "Net-(*2-DOUT)") (class "Default")
      (node (ref "*2") (pin "4") (pinfunction "DOUT_4") (pintype "passive"))
      (node (ref "*3") (pin "2") (pinfunction "DIN_2") (pintype "passive"))
    )
    (net (code "40") (name "Net-(*3-DOUT)") (class "Default")
      (node (ref "*3") (pin "4") (pinfunction "DOUT_4") (pintype "passive"))
      (node (ref "*4") (pin "2") (pinfunction "DIN_2") (pintype "passive"))
    )
    (net (code "41") (name "Net-(*4-DOUT)") (class "Default")
      (node (ref "*4") (pin "4") (pinfunction "DOUT_4") (pintype "passive"))
      (node (ref "*5") (pin "2") (pinfunction "DIN_2") (pintype "passive"))
    )
    (net (code "42") (name "Net-(*5-DOUT)") (class "Default")
      (node (ref "*5") (pin "4") (pinfunction "DOUT_4") (pintype "passive"))
      (node (ref "*6") (pin "2") (pinfunction "DIN_2") (pintype "passive"))
    )
    (net (code "43") (name "Net-(*6-DOUT)") (class "Default")
      (node (ref "*6") (pin "4") (pinfunction "DOUT_4") (pintype "passive"))
      (node (ref "*7") (pin "2") (pinfunction "DIN_2") (pintype "passive"))
    )
    (net (code "44") (name "Net-(*7-DOUT)") (class "Default")
      (node (ref "*7") (pin "4") (pinfunction "DOUT_4") (pintype "passive"))
      (node (ref "*8") (pin "2") (pinfunction "DIN_2") (pintype "passive"))
    )
    (net (code "45") (name "Net-(*8-DOUT)") (class "Default")
      (node (ref "*8") (pin "4") (pinfunction "DOUT_4") (pintype "passive"))
      (node (ref "*9") (pin "2") (pinfunction "DIN_2") (pintype "passive"))
    )
    (net (code "46") (name "Net-(*10-DIN)") (class "Default")
      (node (ref "*10") (pin "2") (pinfunction "DIN_2") (pintype "passive"))
      (node (ref "*9") (pin "4") (pinfunction "DOUT_4") (pintype "passive"))
    )
    (net (code "47") (name "Net-(*10-DOUT)") (class "Default")
      (node (ref "*10") (pin "4") (pinfunction "DOUT_4") (pintype "passive"))
      (node (ref "*11") (pin "2") (pinfunction "DIN_2") (pintype "passive"))
    )
    (net (code "48") (name "Net-(*11-DOUT)") (class "Default")
      (node (ref "*11") (pin "4") (pinfunction "DOUT_4") (pintype "passive"))
      (node (ref "*12") (pin "2") (pinfunction "DIN_2") (pintype "passive"))
    )
    (net (code "49") (name "Net-(*12-DOUT)") (class "Default")
      (node (ref "*12") (pin "4") (pinfunction "DOUT_4") (pintype "passive"))
      (node (ref "*13") (pin "2") (pinfunction "DIN_2") (pintype "passive"))
    )
    (net (code "50") (name "Net-(*13-DOUT)") (class "Default")
      (node (ref "*13") (pin "4") (pinfunction "DOUT_4") (pintype "passive"))
      (node (ref "*14") (pin "2") (pinfunction "DIN_2") (pintype "passive"))
    )
    (net (code "51") (name "Net-(*14-DOUT)") (class "Default")
      (node (ref "*14") (pin "4") (pinfunction "DOUT_4") (pintype "passive"))
      (node (ref "*15") (pin "2") (pinfunction "DIN_2") (pintype "passive"))
    )
    (net (code "52") (name "Net-(*15-DOUT)") (class "Default")
      (node (ref "*15") (pin "4") (pinfunction "DOUT_4") (pintype "passive"))
      (node (ref "*16") (pin "2") (pinfunction "DIN_2") (pintype "passive"))
    )
    (net (code "53") (name "Net-(*17-DOUT)") (class "Default")
      (node (ref "*17") (pin "4") (pinfunction "DOUT_4") (pintype "passive"))
      (node (ref "*18") (pin "2") (pinfunction "DIN_2") (pintype "passive"))
    )
    (net (code "54") (name "Net-(*18-DOUT)") (class "Default")
      (node (ref "*18") (pin "4") (pinfunction "DOUT_4") (pintype "passive"))
      (node (ref "*19") (pin "2") (pinfunction "DIN_2") (pintype "passive"))
    )
    (net (code "55") (name "Net-(*19-DOUT)") (class "Default")
      (node (ref "*19") (pin "4") (pinfunction "DOUT_4") (pintype "passive"))
      (node (ref "*20") (pin "2") (pinfunction "DIN_2") (pintype "passive"))
    )
    (net (code "56") (name "Net-(*20-DOUT)") (class "Default")
      (node (ref "*20") (pin "4") (pinfunction "DOUT_4") (pintype "passive"))
      (node (ref "*21") (pin "2") (pinfunction "DIN_2") (pintype "passive"))
    )
    (net (code "57") (name "Net-(*21-DOUT)") (class "Default")
      (node (ref "*21") (pin "4") (pinfunction "DOUT_4") (pintype "passive"))
      (node (ref "*22") (pin "2") (pinfunction "DIN_2") (pintype "passive"))
    )
    (net (code "58") (name "Net-(*22-DOUT)") (class "Default")
      (node (ref "*22") (pin "4") (pinfunction "DOUT_4") (pintype "passive"))
      (node (ref "*23") (pin "2") (pinfunction "DIN_2") (pintype "passive"))
    )
    (net (code "59") (name "Net-(*23-DOUT)") (class "Default")
      (node (ref "*23") (pin "4") (pinfunction "DOUT_4") (pintype "passive"))
      (node (ref "*24") (pin "2") (pinfunction "DIN_2") (pintype "passive"))
    )
    (net (code "60") (name "Net-(*24-DOUT)") (class "Default")
      (node (ref "*24") (pin "4") (pinfunction "DOUT_4") (pintype "passive"))
      (node (ref "*25") (pin "2") (pinfunction "DIN_2") (pintype "passive"))
    )
    (net (code "61") (name "Net-(*25-DOUT)") (class "Default")
      (node (ref "*25") (pin "4") (pinfunction "DOUT_4") (pintype "passive"))
      (node (ref "*26") (pin "2") (pinfunction "DIN_2") (pintype "passive"))
    )
    (net (code "62") (name "Net-(*26-DOUT)") (class "Default")
      (node (ref "*26") (pin "4") (pinfunction "DOUT_4") (pintype "passive"))
      (node (ref "*27") (pin "2") (pinfunction "DIN_2") (pintype "passive"))
    )
    (net (code "63") (name "Net-(*27-DOUT)") (class "Default")
      (node (ref "*27") (pin "4") (pinfunction "DOUT_4") (pintype "passive"))
      (node (ref "*28") (pin "2") (pinfunction "DIN_2") (pintype "passive"))
    )
    (net (code "64") (name "Net-(*28-DOUT)") (class "Default")
      (node (ref "*28") (pin "4") (pinfunction "DOUT_4") (pintype "passive"))
      (node (ref "*29") (pin "2") (pinfunction "DIN_2") (pintype "passive"))
    )
    (net (code "65") (name "Net-(*29-DOUT)") (class "Default")
      (node (ref "*29") (pin "4") (pinfunction "DOUT_4") (pintype "passive"))
      (node (ref "*30") (pin "2") (pinfunction "DIN_2") (pintype "passive"))
    )
    (net (code "66") (name "Net-(*30-DOUT)") (class "Default")
      (node (ref "*30") (pin "4") (pinfunction "DOUT_4") (pintype "passive"))
      (node (ref "*31") (pin "2") (pinfunction "DIN_2") (pintype "passive"))
    )
    (net (code "67") (name "Net-(*31-DOUT)") (class "Default")
      (node (ref "*31") (pin "4") (pinfunction "DOUT_4") (pintype "passive"))
      (node (ref "*32") (pin "2") (pinfunction "DIN_2") (pintype "passive"))
    )
    (net (code "68") (name "Net-(*32-DOUT)") (class "Default")
      (node (ref "*32") (pin "4") (pinfunction "DOUT_4") (pintype "passive"))
      (node (ref "*33") (pin "2") (pinfunction "DIN_2") (pintype "passive"))
    )
    (net (code "69") (name "Net-(*33-DOUT)") (class "Default")
      (node (ref "*33") (pin "4") (pinfunction "DOUT_4") (pintype "passive"))
      (node (ref "*34") (pin "2") (pinfunction "DIN_2") (pintype "passive"))
    )
    (net (code "70") (name "Net-(*35-DOUT)") (class "Default")
      (node (ref "*35") (pin "4") (pinfunction "DOUT_4") (pintype "passive"))
      (node (ref "*36") (pin "2") (pinfunction "DIN_2") (pintype "passive"))
    )
    (net (code "71") (name "Net-(*36-DOUT)") (class "Default")
      (node (ref "*36") (pin "4") (pinfunction "DOUT_4") (pintype "passive"))
      (node (ref "*37") (pin "2") (pinfunction "DIN_2") (pintype "passive"))
    )
    (net (code "72") (name "Net-(*37-DOUT)") (class "Default")
      (node (ref "*37") (pin "4") (pinfunction "DOUT_4") (pintype "passive"))
      (node (ref "*38") (pin "2") (pinfunction "DIN_2") (pintype "passive"))
    )
    (net (code "73") (name "Net-(*38-DOUT)") (class "Default")
      (node (ref "*38") (pin "4") (pinfunction "DOUT_4") (pintype "passive"))
      (node (ref "*39") (pin "2") (pinfunction "DIN_2") (pintype "passive"))
    )
    (net (code "74") (name "Net-(*39-DOUT)") (class "Default")
      (node (ref "*39") (pin "4") (pinfunction "DOUT_4") (pintype "passive"))
      (node (ref "*40") (pin "2") (pinfunction "DIN_2") (pintype "passive"))
    )
    (net (code "75") (name "Net-(*40-DOUT)") (class "Default")
      (node (ref "*40") (pin "4") (pinfunction "DOUT_4") (pintype "passive"))
      (node (ref "*41") (pin "2") (pinfunction "DIN_2") (pintype "passive"))
    )
    (net (code "76") (name "Net-(*41-DOUT)") (class "Default")
      (node (ref "*41") (pin "4") (pinfunction "DOUT_4") (pintype "passive"))
      (node (ref "*42") (pin "2") (pinfunction "DIN_2") (pintype "passive"))
    )
    (net (code "77") (name "Net-(*42-DOUT)") (class "Default")
      (node (ref "*42") (pin "4") (pinfunction "DOUT_4") (pintype "passive"))
      (node (ref "*43") (pin "2") (pinfunction "DIN_2") (pintype "passive"))
    )
    (net (code "78") (name "Net-(*43-DOUT)") (class "Default")
      (node (ref "*43") (pin "4") (pinfunction "DOUT_4") (pintype "passive"))
      (node (ref "*44") (pin "2") (pinfunction "DIN_2") (pintype "passive"))
    )
    (net (code "79") (name "Net-(*44-DOUT)") (class "Default")
      (node (ref "*44") (pin "4") (pinfunction "DOUT_4") (pintype "passive"))
      (node (ref "*45") (pin "2") (pinfunction "DIN_2") (pintype "passive"))
    )
    (net (code "80") (name "Net-(*45-DOUT)") (class "Default")
      (node (ref "*45") (pin "4") (pinfunction "DOUT_4") (pintype "passive"))
      (node (ref "*46") (pin "2") (pinfunction "DIN_2") (pintype "passive"))
    )
    (net (code "81") (name "Net-(*46-DOUT)") (class "Default")
      (node (ref "*46") (pin "4") (pinfunction "DOUT_4") (pintype "passive"))
      (node (ref "*47") (pin "2") (pinfunction "DIN_2") (pintype "passive"))
    )
    (net (code "82") (name "Net-(*47-DOUT)") (class "Default")
      (node (ref "*47") (pin "4") (pinfunction "DOUT_4") (pintype "passive"))
      (node (ref "*48") (pin "2") (pinfunction "DIN_2") (pintype "passive"))
    )
    (net (code "83") (name "Net-(*48-DOUT)") (class "Default")
      (node (ref "*48") (pin "4") (pinfunction "DOUT_4") (pintype "passive"))
      (node (ref "*49") (pin "2") (pinfunction "DIN_2") (pintype "passive"))
    )
    (net (code "84") (name "Net-(*49-DOUT)") (class "Default")
      (node (ref "*49") (pin "4") (pinfunction "DOUT_4") (pintype "passive"))
      (node (ref "*50") (pin "2") (pinfunction "DIN_2") (pintype "passive"))
    )
    (net (code "85") (name "Net-(*50-DOUT)") (class "Default")
      (node (ref "*50") (pin "4") (pinfunction "DOUT_4") (pintype "passive"))
      (node (ref "*51") (pin "2") (pinfunction "DIN_2") (pintype "passive"))
    )
    (net (code "86") (name "Net-(*52-DOUT)") (class "Default")
      (node (ref "*52") (pin "4") (pinfunction "DOUT_4") (pintype "passive"))
      (node (ref "*53") (pin "2") (pinfunction "DIN_2") (pintype "passive"))
    )
    (net (code "87") (name "Net-(*53-DOUT)") (class "Default")
      (node (ref "*53") (pin "4") (pinfunction "DOUT_4") (pintype "passive"))
      (node (ref "*54") (pin "2") (pinfunction "DIN_2") (pintype "passive"))
    )
    (net (code "88") (name "Net-(*54-DOUT)") (class "Default")
      (node (ref "*54") (pin "4") (pinfunction "DOUT_4") (pintype "passive"))
      (node (ref "*55") (pin "2") (pinfunction "DIN_2") (pintype "passive"))
    )
    (net (code "89") (name "Net-(*55-DOUT)") (class "Default")
      (node (ref "*55") (pin "4") (pinfunction "DOUT_4") (pintype "passive"))
      (node (ref "*56") (pin "2") (pinfunction "DIN_2") (pintype "passive"))
    )
    (net (code "90") (name "Net-(*56-DOUT)") (class "Default")
      (node (ref "*56") (pin "4") (pinfunction "DOUT_4") (pintype "passive"))
      (node (ref "*57") (pin "2") (pinfunction "DIN_2") (pintype "passive"))
    )
    (net (code "91") (name "Net-(*57-DOUT)") (class "Default")
      (node (ref "*57") (pin "4") (pinfunction "DOUT_4") (pintype "passive"))
      (node (ref "*58") (pin "2") (pinfunction "DIN_2") (pintype "passive"))
    )
    (net (code "92") (name "Net-(*58-DOUT)") (class "Default")
      (node (ref "*58") (pin "4") (pinfunction "DOUT_4") (pintype "passive"))
      (node (ref "*59") (pin "2") (pinfunction "DIN_2") (pintype "passive"))
    )
    (net (code "93") (name "Net-(*59-DOUT)") (class "Default")
      (node (ref "*59") (pin "4") (pinfunction "DOUT_4") (pintype "passive"))
      (node (ref "*60") (pin "2") (pinfunction "DIN_2") (pintype "passive"))
    )
    (net (code "94") (name "Net-(*60-DOUT)") (class "Default")
      (node (ref "*60") (pin "4") (pinfunction "DOUT_4") (pintype "passive"))
      (node (ref "*61") (pin "2") (pinfunction "DIN_2") (pintype "passive"))
    )
    (net (code "95") (name "Net-(*61-DOUT)") (class "Default")
      (node (ref "*61") (pin "4") (pinfunction "DOUT_4") (pintype "passive"))
      (node (ref "*62") (pin "2") (pinfunction "DIN_2") (pintype "passive"))
    )
    (net (code "96") (name "Net-(*62-DOUT)") (class "Default")
      (node (ref "*62") (pin "4") (pinfunction "DOUT_4") (pintype "passive"))
      (node (ref "*63") (pin "2") (pinfunction "DIN_2") (pintype "passive"))
    )
    (net (code "97") (name "Net-(*63-DOUT)") (class "Default")
      (node (ref "*63") (pin "4") (pinfunction "DOUT_4") (pintype "passive"))
      (node (ref "*64") (pin "2") (pinfunction "DIN_2") (pintype "passive"))
    )
    (net (code "98") (name "Net-(*64-DOUT)") (class "Default")
      (node (ref "*64") (pin "4") (pinfunction "DOUT_4") (pintype "passive"))
      (node (ref "*65") (pin "2") (pinfunction "DIN_2") (pintype "passive"))
    )
    (net (code "99") (name "Net-(*65-DOUT)") (class "Default")
      (node (ref "*65") (pin "4") (pinfunction "DOUT_4") (pintype "passive"))
      (node (ref "*66") (pin "2") (pinfunction "DIN_2") (pintype "passive"))
    )
    (net (code "100") (name "Net-(*66-DOUT)") (class "Default")
      (node (ref "*66") (pin "4") (pinfunction "DOUT_4") (pintype "passive"))
      (node (ref "*67") (pin "2") (pinfunction "DIN_2") (pintype "passive"))
    )
    (net (code "101") (name "Net-(*67-DOUT)") (class "Default")
      (node (ref "*67") (pin "4") (pinfunction "DOUT_4") (pintype "passive"))
      (node (ref "*68") (pin "2") (pinfunction "DIN_2") (pintype "passive"))
    )
    (net (code "102") (name "Net-(*69-DOUT)") (class "Default")
      (node (ref "*69") (pin "4") (pinfunction "DOUT_4") (pintype "passive"))
      (node (ref "*70") (pin "2") (pinfunction "DIN_2") (pintype "passive"))
    )
    (net (code "103") (name "Net-(*70-DOUT)") (class "Default")
      (node (ref "*70") (pin "4") (pinfunction "DOUT_4") (pintype "passive"))
      (node (ref "*71") (pin "2") (pinfunction "DIN_2") (pintype "passive"))
    )
    (net (code "104") (name "Net-(*71-DOUT)") (class "Default")
      (node (ref "*71") (pin "4") (pinfunction "DOUT_4") (pintype "passive"))
      (node (ref "*72") (pin "2") (pinfunction "DIN_2") (pintype "passive"))
    )
    (net (code "105") (name "Net-(*72-DOUT)") (class "Default")
      (node (ref "*72") (pin "4") (pinfunction "DOUT_4") (pintype "passive"))
      (node (ref "*73") (pin "2") (pinfunction "DIN_2") (pintype "passive"))
    )
    (net (code "106") (name "Net-(*73-DOUT)") (class "Default")
      (node (ref "*73") (pin "4") (pinfunction "DOUT_4") (pintype "passive"))
      (node (ref "*74") (pin "2") (pinfunction "DIN_2") (pintype "passive"))
    )
    (net (code "107") (name "Net-(*74-DOUT)") (class "Default")
      (node (ref "*74") (pin "4") (pinfunction "DOUT_4") (pintype "passive"))
      (node (ref "*75") (pin "2") (pinfunction "DIN_2") (pintype "passive"))
    )
    (net (code "108") (name "Net-(*75-DOUT)") (class "Default")
      (node (ref "*75") (pin "4") (pinfunction "DOUT_4") (pintype "passive"))
      (node (ref "*76") (pin "2") (pinfunction "DIN_2") (pintype "passive"))
    )
    (net (code "109") (name "Net-(*76-DOUT)") (class "Default")
      (node (ref "*76") (pin "4") (pinfunction "DOUT_4") (pintype "passive"))
      (node (ref "*77") (pin "2") (pinfunction "DIN_2") (pintype "passive"))
    )
    (net (code "110") (name "Net-(*77-DOUT)") (class "Default")
      (node (ref "*77") (pin "4") (pinfunction "DOUT_4") (pintype "passive"))
      (node (ref "*78") (pin "2") (pinfunction "DIN_2") (pintype "passive"))
    )
    (net (code "111") (name "Net-(*78-DOUT)") (class "Default")
      (node (ref "*78") (pin "4") (pinfunction "DOUT_4") (pintype "passive"))
      (node (ref "*79") (pin "2") (pinfunction "DIN_2") (pintype "passive"))
    )
    (net (code "112") (name "Net-(*79-DOUT)") (class "Default")
      (node (ref "*79") (pin "4") (pinfunction "DOUT_4") (pintype "passive"))
      (node (ref "*80") (pin "2") (pinfunction "DIN_2") (pintype "passive"))
    )
    (net (code "113") (name "Net-(*80-DOUT)") (class "Default")
      (node (ref "*80") (pin "4") (pinfunction "DOUT_4") (pintype "passive"))
      (node (ref "*81") (pin "2") (pinfunction "DIN_2") (pintype "passive"))
    )
    (net (code "114") (name "Net-(*81-DOUT)") (class "Default")
      (node (ref "*81") (pin "4") (pinfunction "DOUT_4") (pintype "passive"))
      (node (ref "*82") (pin "2") (pinfunction "DIN_2") (pintype "passive"))
    )
    (net (code "115") (name "Net-(*82-DOUT)") (class "Default")
      (node (ref "*82") (pin "4") (pinfunction "DOUT_4") (pintype "passive"))
      (node (ref "*83") (pin "2") (pinfunction "DIN_2") (pintype "passive"))
    )
    (net (code "116") (name "Net-(*83-DOUT)") (class "Default")
      (node (ref "*83") (pin "4") (pinfunction "DOUT_4") (pintype "passive"))
      (node (ref "*84") (pin "2") (pinfunction "DIN_2") (pintype "passive"))
    )
    (net (code "117") (name "Net-(*84-DOUT)") (class "Default")
      (node (ref "*84") (pin "4") (pinfunction "DOUT_4") (pintype "passive"))
      (node (ref "*85") (pin "2") (pinfunction "DIN_2") (pintype "passive"))
    )
    (net (code "118") (name "Net-(*85-DOUT)") (class "Default")
      (node (ref "*85") (pin "4") (pinfunction "DOUT_4") (pintype "passive"))
      (node (ref "*86") (pin "2") (pinfunction "DIN_2") (pintype "passive"))
    )
    (net (code "119") (name "Net-(*87-DOUT)") (class "Default")
      (node (ref "*87") (pin "4") (pinfunction "DOUT_4") (pintype "passive"))
      (node (ref "*88") (pin "2") (pinfunction "DIN_2") (pintype "passive"))
    )
    (net (code "120") (name "Net-(*88-DOUT)") (class "Default")
      (node (ref "*88") (pin "4") (pinfunction "DOUT_4") (pintype "passive"))
      (node (ref "*89") (pin "2") (pinfunction "DIN_2") (pintype "passive"))
    )
    (net (code "121") (name "Net-(*89-DOUT)") (class "Default")
      (node (ref "*89") (pin "4") (pinfunction "DOUT_4") (pintype "passive"))
      (node (ref "*90") (pin "2") (pinfunction "DIN_2") (pintype "passive"))
    )
    (net (code "122") (name "Net-(*90-DOUT)") (class "Default")
      (node (ref "*90") (pin "4") (pinfunction "DOUT_4") (pintype "passive"))
      (node (ref "*91") (pin "2") (pinfunction "DIN_2") (pintype "passive"))
    )
    (net (code "123") (name "Net-(*91-DOUT)") (class "Default")
      (node (ref "*91") (pin "4") (pinfunction "DOUT_4") (pintype "passive"))
      (node (ref "*92") (pin "2") (pinfunction "DIN_2") (pintype "passive"))
    )
    (net (code "124") (name "Net-(*92-DOUT)") (class "Default")
      (node (ref "*92") (pin "4") (pinfunction "DOUT_4") (pintype "passive"))
      (node (ref "*93") (pin "2") (pinfunction "DIN_2") (pintype "passive"))
    )
    (net (code "125") (name "Net-(*93-DOUT)") (class "Default")
      (node (ref "*93") (pin "4") (pinfunction "DOUT_4") (pintype "passive"))
      (node (ref "*94") (pin "2") (pinfunction "DIN_2") (pintype "passive"))
    )
    (net (code "126") (name "Net-(*94-DOUT)") (class "Default")
      (node (ref "*94") (pin "4") (pinfunction "DOUT_4") (pintype "passive"))
      (node (ref "*95") (pin "2") (pinfunction "DIN_2") (pintype "passive"))
    )
    (net (code "127") (name "Net-(*95-DOUT)") (class "Default")
      (node (ref "*95") (pin "4") (pinfunction "DOUT_4") (pintype "passive"))
      (node (ref "*96") (pin "2") (pinfunction "DIN_2") (pintype "passive"))
    )
    (net (code "128") (name "Net-(*96-DOUT)") (class "Default")
      (node (ref "*96") (pin "4") (pinfunction "DOUT_4") (pintype "passive"))
      (node (ref "*97") (pin "2") (pinfunction "DIN_2") (pintype "passive"))
    )
    (net (code "129") (name "Net-(*97-DOUT)") (class "Default")
      (node (ref "*97") (pin "4") (pinfunction "DOUT_4") (pintype "passive"))
      (node (ref "*98") (pin "2") (pinfunction "DIN_2") (pintype "passive"))
    )
    (net (code "130") (name "Net-(*98-DOUT)") (class "Default")
      (node (ref "*98") (pin "4") (pinfunction "DOUT_4") (pintype "passive"))
      (node (ref "*99") (pin "2") (pinfunction "DIN_2") (pintype "passive"))
    )
    (net (code "131") (name "Net-(*100-DIN)") (class "Default")
      (node (ref "*100") (pin "2") (pinfunction "DIN_2") (pintype "passive"))
      (node (ref "*99") (pin "4") (pinfunction "DOUT_4") (pintype "passive"))
    )
    (net (code "132") (name "Net-(*100-DOUT)") (class "Default")
      (node (ref "*100") (pin "4") (pinfunction "DOUT_4") (pintype "passive"))
      (node (ref "*101") (pin "2") (pinfunction "DIN_2") (pintype "passive"))
    )
    (net (code "133") (name "Net-(*101-DOUT)") (class "Default")
      (node (ref "*101") (pin "4") (pinfunction "DOUT_4") (pintype "passive"))
      (node (ref "*102") (pin "2") (pinfunction "DIN_2") (pintype "passive"))
    )
    (net (code "134") (name "Net-(*102-DOUT)") (class "Default")
      (node (ref "*102") (pin "4") (pinfunction "DOUT_4") (pintype "passive"))
      (node (ref "*103") (pin "2") (pinfunction "DIN_2") (pintype "passive"))
    )
    (net (code "135") (name "Net-(*103-DOUT)") (class "Default")
      (node (ref "*103") (pin "4") (pinfunction "DOUT_4") (pintype "passive"))
      (node (ref "*104") (pin "2") (pinfunction "DIN_2") (pintype "passive"))
    )
    (net (code "136") (name "Net-(SW1-2)") (class "Default")
      (node (ref "D4") (pin "1") (pinfunction "1_1") (pintype "passive"))
      (node (ref "SW1") (pin "1") (pinfunction "2_1") (pintype "passive"))
    )
    (net (code "137") (name "Net-(SW2-2)") (class "Default")
      (node (ref "D5") (pin "1") (pinfunction "1_1") (pintype "passive"))
      (node (ref "SW2") (pin "1") (pinfunction "2_1") (pintype "passive"))
    )
    (net (code "138") (name "Net-(SW3-2)") (class "Default")
      (node (ref "D6") (pin "1") (pinfunction "1_1") (pintype "passive"))
      (node (ref "SW3") (pin "1") (pinfunction "2_1") (pintype "passive"))
    )
    (net (code "139") (name "Net-(SW4-2)") (class "Default")
      (node (ref "D7") (pin "1") (pinfunction "1_1") (pintype "passive"))
      (node (ref "SW4") (pin "1") (pinfunction "2_1") (pintype "passive"))
    )
    (net (code "140") (name "Net-(SW5-2)") (class "Default")
      (node (ref "D8") (pin "1") (pinfunction "1_1") (pintype "passive"))
      (node (ref "SW5") (pin "1") (pinfunction "2_1") (pintype "passive"))
    )
    (net (code "141") (name "Net-(SW6-2)") (class "Default")
      (node (ref "D9") (pin "1") (pinfunction "1_1") (pintype "passive"))
      (node (ref "SW6") (pin "1") (pinfunction "2_1") (pintype "passive"))
    )
    (net (code "142") (name "Net-(SW7-2)") (class "Default")
      (node (ref "D10") (pin "1") (pinfunction "1_1") (pintype "passive"))
      (node (ref "SW7") (pin "1") (pinfunction "2_1") (pintype "passive"))
    )
    (net (code "143") (name "Net-(SW8-2)") (class "Default")
      (node (ref "D11") (pin "1") (pinfunction "1_1") (pintype "passive"))
      (node (ref "SW8") (pin "1") (pinfunction "2_1") (pintype "passive"))
    )
    (net (code "144") (name "Net-(SW9-2)") (class "Default")
      (node (ref "D12") (pin "1") (pinfunction "1_1") (pintype "passive"))
      (node (ref "SW9") (pin "1") (pinfunction "2_1") (pintype "passive"))
    )
    (net (code "145") (name "Net-(SW10-2)") (class "Default")
      (node (ref "D13") (pin "1") (pinfunction "1_1") (pintype "passive"))
      (node (ref "SW10") (pin "1") (pinfunction "2_1") (pintype "passive"))
    )
    (net (code "146") (name "Net-(SW11-2)") (class "Default")
      (node (ref "D14") (pin "1") (pinfunction "1_1") (pintype "passive"))
      (node (ref "SW11") (pin "1") (pinfunction "2_1") (pintype "passive"))
    )
    (net (code "147") (name "Net-(SW12-2)") (class "Default")
      (node (ref "D15") (pin "1") (pinfunction "1_1") (pintype "passive"))
      (node (ref "SW12") (pin "1") (pinfunction "2_1") (pintype "passive"))
    )
    (net (code "148") (name "Net-(SW13-2)") (class "Default")
      (node (ref "D16") (pin "1") (pinfunction "1_1") (pintype "passive"))
      (node (ref "SW13") (pin "1") (pinfunction "2_1") (pintype "passive"))
    )
    (net (code "149") (name "Net-(SW14-2)") (class "Default")
      (node (ref "D17") (pin "1") (pinfunction "1_1") (pintype "passive"))
      (node (ref "SW14") (pin "1") (pinfunction "2_1") (pintype "passive"))
    )
    (net (code "150") (name "Net-(SW15-2)") (class "Default")
      (node (ref "D18") (pin "1") (pinfunction "1_1") (pintype "passive"))
      (node (ref "SW15") (pin "1") (pinfunction "2_1") (pintype "passive"))
    )
    (net (code "151") (name "Net-(SW16-2)") (class "Default")
      (node (ref "D19") (pin "1") (pinfunction "1_1") (pintype "passive"))
      (node (ref "SW16") (pin "1") (pinfunction "2_1") (pintype "passive"))
    )
    (net (code "152") (name "Net-(SW17-2)") (class "Default")
      (node (ref "D20") (pin "1") (pinfunction "1_1") (pintype "passive"))
      (node (ref "SW17") (pin "1") (pinfunction "2_1") (pintype "passive"))
    )
    (net (code "153") (name "Net-(SW18-2)") (class "Default")
      (node (ref "D21") (pin "1") (pinfunction "1_1") (pintype "passive"))
      (node (ref "SW18") (pin "1") (pinfunction "2_1") (pintype "passive"))
    )
    (net (code "154") (name "Net-(SW19-2)") (class "Default")
      (node (ref "D22") (pin "1") (pinfunction "1_1") (pintype "passive"))
      (node (ref "SW19") (pin "1") (pinfunction "2_1") (pintype "passive"))
    )
    (net (code "155") (name "Net-(SW20-2)") (class "Default")
      (node (ref "D23") (pin "1") (pinfunction "1_1") (pintype "passive"))
      (node (ref "SW20") (pin "1") (pinfunction "2_1") (pintype "passive"))
    )
    (net (code "156") (name "Net-(SW21-2)") (class "Default")
      (node (ref "D24") (pin "1") (pinfunction "1_1") (pintype "passive"))
      (node (ref "SW21") (pin "1") (pinfunction "2_1") (pintype "passive"))
    )
    (net (code "157") (name "Net-(SW22-2)") (class "Default")
      (node (ref "D25") (pin "1") (pinfunction "1_1") (pintype "passive"))
      (node (ref "SW22") (pin "1") (pinfunction "2_1") (pintype "passive"))
    )
    (net (code "158") (name "Net-(SW23-2)") (class "Default")
      (node (ref "D26") (pin "1") (pinfunction "1_1") (pintype "passive"))
      (node (ref "SW23") (pin "1") (pinfunction "2_1") (pintype "passive"))
    )
    (net (code "159") (name "Net-(SW24-2)") (class "Default")
      (node (ref "D27") (pin "1") (pinfunction "1_1") (pintype "passive"))
      (node (ref "SW24") (pin "1") (pinfunction "2_1") (pintype "passive"))
    )
    (net (code "160") (name "Net-(SW25-2)") (class "Default")
      (node (ref "D28") (pin "1") (pinfunction "1_1") (pintype "passive"))
      (node (ref "SW25") (pin "1") (pinfunction "2_1") (pintype "passive"))
    )
    (net (code "161") (name "Net-(SW26-2)") (class "Default")
      (node (ref "D29") (pin "1") (pinfunction "1_1") (pintype "passive"))
      (node (ref "SW26") (pin "1") (pinfunction "2_1") (pintype "passive"))
    )
    (net (code "162") (name "Net-(SW27-2)") (class "Default")
      (node (ref "D30") (pin "1") (pinfunction "1_1") (pintype "passive"))
      (node (ref "SW27") (pin "1") (pinfunction "2_1") (pintype "passive"))
    )
    (net (code "163") (name "Net-(SW28-2)") (class "Default")
      (node (ref "D31") (pin "1") (pinfunction "1_1") (pintype "passive"))
      (node (ref "SW28") (pin "1") (pinfunction "2_1") (pintype "passive"))
    )
    (net (code "164") (name "Net-(SW29-2)") (class "Default")
      (node (ref "D32") (pin "1") (pinfunction "1_1") (pintype "passive"))
      (node (ref "SW29") (pin "1") (pinfunction "2_1") (pintype "passive"))
    )
    (net (code "165") (name "Net-(SW30-2)") (class "Default")
      (node (ref "D33") (pin "1") (pinfunction "1_1") (pintype "passive"))
      (node (ref "SW30") (pin "1") (pinfunction "2_1") (pintype "passive"))
    )
    (net (code "166") (name "Net-(SW31-2)") (class "Default")
      (node (ref "D34") (pin "1") (pinfunction "1_1") (pintype "passive"))
      (node (ref "SW31") (pin "1") (pinfunction "2_1") (pintype "passive"))
    )
    (net (code "167") (name "Net-(SW32-2)") (class "Default")
      (node (ref "D35") (pin "1") (pinfunction "1_1") (pintype "passive"))
      (node (ref "SW32") (pin "1") (pinfunction "2_1") (pintype "passive"))
    )
    (net (code "168") (name "Net-(SW33-2)") (class "Default")
      (node (ref "D36") (pin "1") (pinfunction "1_1") (pintype "passive"))
      (node (ref "SW33") (pin "1") (pinfunction "2_1") (pintype "passive"))
    )
    (net (code "169") (name "Net-(SW34-2)") (class "Default")
      (node (ref "D37") (pin "1") (pinfunction "1_1") (pintype "passive"))
      (node (ref "SW34") (pin "1") (pinfunction "2_1") (pintype "passive"))
    )
    (net (code "170") (name "Net-(SW35-2)") (class "Default")
      (node (ref "D38") (pin "1") (pinfunction "1_1") (pintype "passive"))
      (node (ref "SW35") (pin "1") (pinfunction "2_1") (pintype "passive"))
    )
    (net (code "171") (name "Net-(SW36-2)") (class "Default")
      (node (ref "D39") (pin "1") (pinfunction "1_1") (pintype "passive"))
      (node (ref "SW36") (pin "1") (pinfunction "2_1") (pintype "passive"))
    )
    (net (code "172") (name "Net-(SW37-2)") (class "Default")
      (node (ref "D40") (pin "1") (pinfunction "1_1") (pintype "passive"))
      (node (ref "SW37") (pin "1") (pinfunction "2_1") (pintype "passive"))
    )
    (net (code "173") (name "Net-(SW38-2)") (class "Default")
      (node (ref "D41") (pin "1") (pinfunction "1_1") (pintype "passive"))
      (node (ref "SW38") (pin "1") (pinfunction "2_1") (pintype "passive"))
    )
    (net (code "174") (name "Net-(SW39-2)") (class "Default")
      (node (ref "D42") (pin "1") (pinfunction "1_1") (pintype "passive"))
      (node (ref "SW39") (pin "1") (pinfunction "2_1") (pintype "passive"))
    )
    (net (code "175") (name "Net-(SW40-2)") (class "Default")
      (node (ref "D43") (pin "1") (pinfunction "1_1") (pintype "passive"))
      (node (ref "SW40") (pin "1") (pinfunction "2_1") (pintype "passive"))
    )
    (net (code "176") (name "Net-(SW41-2)") (class "Default")
      (node (ref "D44") (pin "1") (pinfunction "1_1") (pintype "passive"))
      (node (ref "SW41") (pin "1") (pinfunction "2_1") (pintype "passive"))
    )
    (net (code "177") (name "Net-(SW42-2)") (class "Default")
      (node (ref "D45") (pin "1") (pinfunction "1_1") (pintype "passive"))
      (node (ref "SW42") (pin "1") (pinfunction "2_1") (pintype "passive"))
    )
    (net (code "178") (name "Net-(SW43-2)") (class "Default")
      (node (ref "D46") (pin "1") (pinfunction "1_1") (pintype "passive"))
      (node (ref "SW43") (pin "1") (pinfunction "2_1") (pintype "passive"))
    )
    (net (code "179") (name "Net-(SW44-2)") (class "Default")
      (node (ref "D47") (pin "1") (pinfunction "1_1") (pintype "passive"))
      (node (ref "SW44") (pin "1") (pinfunction "2_1") (pintype "passive"))
    )
    (net (code "180") (name "Net-(SW45-2)") (class "Default")
      (node (ref "D48") (pin "1") (pinfunction "1_1") (pintype "passive"))
      (node (ref "SW45") (pin "1") (pinfunction "2_1") (pintype "passive"))
    )
    (net (code "181") (name "Net-(SW46-2)") (class "Default")
      (node (ref "D49") (pin "1") (pinfunction "1_1") (pintype "passive"))
      (node (ref "SW46") (pin "1") (pinfunction "2_1") (pintype "passive"))
    )
    (net (code "182") (name "Net-(SW47-2)") (class "Default")
      (node (ref "D50") (pin "1") (pinfunction "1_1") (pintype "passive"))
      (node (ref "SW47") (pin "1") (pinfunction "2_1") (pintype "passive"))
    )
    (net (code "183") (name "Net-(SW48-2)") (class "Default")
      (node (ref "D51") (pin "1") (pinfunction "1_1") (pintype "passive"))
      (node (ref "SW48") (pin "1") (pinfunction "2_1") (pintype "passive"))
    )
    (net (code "184") (name "Net-(SW49-2)") (class "Default")
      (node (ref "D52") (pin "1") (pinfunction "1_1") (pintype "passive"))
      (node (ref "SW49") (pin "1") (pinfunction "2_1") (pintype "passive"))
    )
    (net (code "185") (name "Net-(SW50-2)") (class "Default")
      (node (ref "D53") (pin "1") (pinfunction "1_1") (pintype "passive"))
      (node (ref "SW50") (pin "1") (pinfunction "2_1") (pintype "passive"))
    )
    (net (code "186") (name "Net-(SW51-2)") (class "Default")
      (node (ref "D54") (pin "1") (pinfunction "1_1") (pintype "passive"))
      (node (ref "SW51") (pin "1") (pinfunction "2_1") (pintype "passive"))
    )
    (net (code "187") (name "Net-(SW52-2)") (class "Default")
      (node (ref "D55") (pin "1") (pinfunction "1_1") (pintype "passive"))
      (node (ref "SW52") (pin "1") (pinfunction "2_1") (pintype "passive"))
    )
    (net (code "188") (name "Net-(SW53-2)") (class "Default")
      (node (ref "D56") (pin "1") (pinfunction "1_1") (pintype "passive"))
      (node (ref "SW53") (pin "1") (pinfunction "2_1") (pintype "passive"))
    )
    (net (code "189") (name "Net-(SW54-2)") (class "Default")
      (node (ref "D57") (pin "1") (pinfunction "1_1") (pintype "passive"))
      (node (ref "SW54") (pin "1") (pinfunction "2_1") (pintype "passive"))
    )
    (net (code "190") (name "Net-(SW55-2)") (class "Default")
      (node (ref "D58") (pin "1") (pinfunction "1_1") (pintype "passive"))
      (node (ref "SW55") (pin "1") (pinfunction "2_1") (pintype "passive"))
    )
    (net (code "191") (name "Net-(SW56-2)") (class "Default")
      (node (ref "D59") (pin "1") (pinfunction "1_1") (pintype "passive"))
      (node (ref "SW56") (pin "1") (pinfunction "2_1") (pintype "passive"))
    )
    (net (code "192") (name "Net-(SW57-2)") (class "Default")
      (node (ref "D60") (pin "1") (pinfunction "1_1") (pintype "passive"))
      (node (ref "SW57") (pin "1") (pinfunction "2_1") (pintype "passive"))
    )
    (net (code "193") (name "Net-(SW58-2)") (class "Default")
      (node (ref "D61") (pin "1") (pinfunction "1_1") (pintype "passive"))
      (node (ref "SW58") (pin "1") (pinfunction "2_1") (pintype "passive"))
    )
    (net (code "194") (name "Net-(SW59-2)") (class "Default")
      (node (ref "D62") (pin "1") (pinfunction "1_1") (pintype "passive"))
      (node (ref "SW59") (pin "1") (pinfunction "2_1") (pintype "passive"))
    )
    (net (code "195") (name "Net-(SW60-2)") (class "Default")
      (node (ref "D63") (pin "1") (pinfunction "1_1") (pintype "passive"))
      (node (ref "SW60") (pin "1") (pinfunction "2_1") (pintype "passive"))
    )
    (net (code "196") (name "Net-(SW61-2)") (class "Default")
      (node (ref "D64") (pin "1") (pinfunction "1_1") (pintype "passive"))
      (node (ref "SW61") (pin "1") (pinfunction "2_1") (pintype "passive"))
    )
    (net (code "197") (name "Net-(SW62-2)") (class "Default")
      (node (ref "D65") (pin "1") (pinfunction "1_1") (pintype "passive"))
      (node (ref "SW62") (pin "1") (pinfunction "2_1") (pintype "passive"))
    )
    (net (code "198") (name "Net-(SW63-2)") (class "Default")
      (node (ref "D66") (pin "1") (pinfunction "1_1") (pintype "passive"))
      (node (ref "SW63") (pin "1") (pinfunction "2_1") (pintype "passive"))
    )
    (net (code "199") (name "Net-(SW64-2)") (class "Default")
      (node (ref "D67") (pin "1") (pinfunction "1_1") (pintype "passive"))
      (node (ref "SW64") (pin "1") (pinfunction "2_1") (pintype "passive"))
    )
    (net (code "200") (name "Net-(SW65-2)") (class "Default")
      (node (ref "D68") (pin "1") (pinfunction "1_1") (pintype "passive"))
      (node (ref "SW65") (pin "1") (pinfunction "2_1") (pintype "passive"))
    )
    (net (code "201") (name "Net-(SW66-2)") (class "Default")
      (node (ref "D69") (pin "1") (pinfunction "1_1") (pintype "passive"))
      (node (ref "SW66") (pin "1") (pinfunction "2_1") (pintype "passive"))
    )
    (net (code "202") (name "Net-(SW67-2)") (class "Default")
      (node (ref "D70") (pin "1") (pinfunction "1_1") (pintype "passive"))
      (node (ref "SW67") (pin "1") (pinfunction "2_1") (pintype "passive"))
    )
    (net (code "203") (name "Net-(SW68-2)") (class "Default")
      (node (ref "D71") (pin "1") (pinfunction "1_1") (pintype "passive"))
      (node (ref "SW68") (pin "1") (pinfunction "2_1") (pintype "passive"))
    )
    (net (code "204") (name "Net-(SW69-2)") (class "Default")
      (node (ref "D72") (pin "1") (pinfunction "1_1") (pintype "passive"))
      (node (ref "SW69") (pin "1") (pinfunction "2_1") (pintype "passive"))
    )
    (net (code "205") (name "Net-(SW70-2)") (class "Default")
      (node (ref "D73") (pin "1") (pinfunction "1_1") (pintype "passive"))
      (node (ref "SW70") (pin "1") (pinfunction "2_1") (pintype "passive"))
    )
    (net (code "206") (name "Net-(SW71-2)") (class "Default")
      (node (ref "D74") (pin "1") (pinfunction "1_1") (pintype "passive"))
      (node (ref "SW71") (pin "1") (pinfunction "2_1") (pintype "passive"))
    )
    (net (code "207") (name "Net-(SW72-2)") (class "Default")
      (node (ref "D75") (pin "1") (pinfunction "1_1") (pintype "passive"))
      (node (ref "SW72") (pin "1") (pinfunction "2_1") (pintype "passive"))
    )
    (net (code "208") (name "Net-(SW73-2)") (class "Default")
      (node (ref "D76") (pin "1") (pinfunction "1_1") (pintype "passive"))
      (node (ref "SW73") (pin "1") (pinfunction "2_1") (pintype "passive"))
    )
    (net (code "209") (name "Net-(SW74-2)") (class "Default")
      (node (ref "D77") (pin "1") (pinfunction "1_1") (pintype "passive"))
      (node (ref "SW74") (pin "1") (pinfunction "2_1") (pintype "passive"))
    )
    (net (code "210") (name "Net-(SW75-2)") (class "Default")
      (node (ref "D78") (pin "1") (pinfunction "1_1") (pintype "passive"))
      (node (ref "SW75") (pin "1") (pinfunction "2_1") (pintype "passive"))
    )
    (net (code "211") (name "Net-(SW76-2)") (class "Default")
      (node (ref "D79") (pin "1") (pinfunction "1_1") (pintype "passive"))
      (node (ref "SW76") (pin "1") (pinfunction "2_1") (pintype "passive"))
    )
    (net (code "212") (name "Net-(SW77-2)") (class "Default")
      (node (ref "D80") (pin "1") (pinfunction "1_1") (pintype "passive"))
      (node (ref "SW77") (pin "1") (pinfunction "2_1") (pintype "passive"))
    )
    (net (code "213") (name "Net-(SW78-2)") (class "Default")
      (node (ref "D81") (pin "1") (pinfunction "1_1") (pintype "passive"))
      (node (ref "SW78") (pin "1") (pinfunction "2_1") (pintype "passive"))
    )
    (net (code "214") (name "Net-(SW79-2)") (class "Default")
      (node (ref "D82") (pin "1") (pinfunction "1_1") (pintype "passive"))
      (node (ref "SW79") (pin "1") (pinfunction "2_1") (pintype "passive"))
    )
    (net (code "215") (name "Net-(SW80-2)") (class "Default")
      (node (ref "D83") (pin "1") (pinfunction "1_1") (pintype "passive"))
      (node (ref "SW80") (pin "1") (pinfunction "2_1") (pintype "passive"))
    )
    (net (code "216") (name "Net-(SW81-2)") (class "Default")
      (node (ref "D84") (pin "1") (pinfunction "1_1") (pintype "passive"))
      (node (ref "SW81") (pin "1") (pinfunction "2_1") (pintype "passive"))
    )
    (net (code "217") (name "Net-(SW82-2)") (class "Default")
      (node (ref "D85") (pin "1") (pinfunction "1_1") (pintype "passive"))
      (node (ref "SW82") (pin "1") (pinfunction "2_1") (pintype "passive"))
    )
    (net (code "218") (name "Net-(SW83-2)") (class "Default")
      (node (ref "D86") (pin "1") (pinfunction "1_1") (pintype "passive"))
      (node (ref "SW83") (pin "1") (pinfunction "2_1") (pintype "passive"))
    )
    (net (code "219") (name "Net-(SW84-2)") (class "Default")
      (node (ref "D87") (pin "1") (pinfunction "1_1") (pintype "passive"))
      (node (ref "SW84") (pin "1") (pinfunction "2_1") (pintype "passive"))
    )
    (net (code "220") (name "Net-(SW85-2)") (class "Default")
      (node (ref "D88") (pin "1") (pinfunction "1_1") (pintype "passive"))
      (node (ref "SW85") (pin "1") (pinfunction "2_1") (pintype "passive"))
    )
    (net (code "221") (name "Net-(SW86-2)") (class "Default")
      (node (ref "D89") (pin "1") (pinfunction "1_1") (pintype "passive"))
      (node (ref "SW86") (pin "1") (pinfunction "2_1") (pintype "passive"))
    )
    (net (code "222") (name "Net-(SW87-2)") (class "Default")
      (node (ref "D90") (pin "1") (pinfunction "1_1") (pintype "passive"))
      (node (ref "SW87") (pin "1") (pinfunction "2_1") (pintype "passive"))
    )
    (net (code "223") (name "Net-(SW88-2)") (class "Default")
      (node (ref "D91") (pin "1") (pinfunction "1_1") (pintype "passive"))
      (node (ref "SW88") (pin "1") (pinfunction "2_1") (pintype "passive"))
    )
    (net (code "224") (name "Net-(SW89-2)") (class "Default")
      (node (ref "D92") (pin "1") (pinfunction "1_1") (pintype "passive"))
      (node (ref "SW89") (pin "1") (pinfunction "2_1") (pintype "passive"))
    )
    (net (code "225") (name "Net-(SW90-2)") (class "Default")
      (node (ref "D93") (pin "1") (pinfunction "1_1") (pintype "passive"))
      (node (ref "SW90") (pin "1") (pinfunction "2_1") (pintype "passive"))
    )
    (net (code "226") (name "Net-(SW91-2)") (class "Default")
      (node (ref "D94") (pin "1") (pinfunction "1_1") (pintype "passive"))
      (node (ref "SW91") (pin "1") (pinfunction "2_1") (pintype "passive"))
    )
    (net (code "227") (name "Net-(SW92-2)") (class "Default")
      (node (ref "D95") (pin "1") (pinfunction "1_1") (pintype "passive"))
      (node (ref "SW92") (pin "1") (pinfunction "2_1") (pintype "passive"))
    )
    (net (code "228") (name "Net-(SW93-2)") (class "Default")
      (node (ref "D96") (pin "1") (pinfunction "1_1") (pintype "passive"))
      (node (ref "SW93") (pin "1") (pinfunction "2_1") (pintype "passive"))
    )
    (net (code "229") (name "Net-(SW94-2)") (class "Default")
      (node (ref "D97") (pin "1") (pinfunction "1_1") (pintype "passive"))
      (node (ref "SW94") (pin "1") (pinfunction "2_1") (pintype "passive"))
    )
    (net (code "230") (name "Net-(SW95-2)") (class "Default")
      (node (ref "D98") (pin "1") (pinfunction "1_1") (pintype "passive"))
      (node (ref "SW95") (pin "1") (pinfunction "2_1") (pintype "passive"))
    )
    (net (code "231") (name "Net-(SW96-2)") (class "Default")
      (node (ref "D99") (pin "1") (pinfunction "1_1") (pintype "passive"))
      (node (ref "SW96") (pin "1") (pinfunction "2_1") (pintype "passive"))
    )
    (net (code "232") (name "Net-(SW97-2)") (class "Default")
      (node (ref "D100") (pin "1") (pinfunction "1_1") (pintype "passive"))
      (node (ref "SW97") (pin "1") (pinfunction "2_1") (pintype "passive"))
    )
    (net (code "233") (name "Net-(SW98-2)") (class "Default")
      (node (ref "D101") (pin "1") (pinfunction "1_1") (pintype "passive"))
      (node (ref "SW98") (pin "1") (pinfunction "2_1") (pintype "passive"))
    )
    (net (code "234") (name "Net-(SW99-2)") (class "Default")
      (node (ref "D102") (pin "1") (pinfunction "1_1") (pintype "passive"))
      (node (ref "SW99") (pin "1") (pinfunction "2_1") (pintype "passive"))
    )
    (net (code "235") (name "Net-(SW100-2)") (class "Default")
      (node (ref "D103") (pin "1") (pinfunction "1_1") (pintype "passive"))
      (node (ref "SW100") (pin "1") (pinfunction "2_1") (pintype "passive"))
    )
    (net (code "236") (name "Net-(SW101-2)") (class "Default")
      (node (ref "D104") (pin "1") (pinfunction "1_1") (pintype "passive"))
      (node (ref "SW101") (pin "1") (pinfunction "2_1") (pintype "passive"))
    )
    (net (code "237") (name "Net-(SW102-2)") (class "Default")
      (node (ref "D105") (pin "1") (pinfunction "1_1") (pintype "passive"))
      (node (ref "SW102") (pin "1") (pinfunction "2_1") (pintype "passive"))
    )
    (net (code "238") (name "Net-(SW103-2)") (class "Default")
      (node (ref "D106") (pin "1") (pinfunction "1_1") (pintype "passive"))
      (node (ref "SW103") (pin "1") (pinfunction "2_1") (pintype "passive"))
    )
    (net (code "239") (name "Net-(SW104-2)") (class "Default")
      (node (ref "D107") (pin "1") (pinfunction "1_1") (pintype "passive"))
      (node (ref "SW104") (pin "1") (pinfunction "2_1") (pintype "passive"))
    )
    (net (code "240") (name "Net-(U2-P3.0)") (class "Default")
      (node (ref "U2") (pin "5") (pinfunction "P3.0_5") (pintype "passive"))
      (node (ref "U8") (pin "2") (pinfunction "TXD_2") (pintype "passive"))
    )
    (net (code "241") (name "Net-(U2-P3.1)") (class "Default")
      (node (ref "U2") (pin "6") (pinfunction "P3.1_6") (pintype "passive"))
      (node (ref "U8") (pin "3") (pinfunction "RXD_3") (pintype "passive"))
    )
    (net (code "242") (name "Net-(U3-UD+)") (class "Default")
      (node (ref "U3") (pin "12") (pinfunction "UD+_12") (pintype "passive"))
      (node (ref "U4") (pin "3") (pinfunction "D+_3") (pintype "passive"))
    )
    (net (code "243") (name "Net-(U3-UD-)") (class "Default")
      (node (ref "U3") (pin "13") (pinfunction "UD-_13") (pintype "passive"))
      (node (ref "U4") (pin "2") (pinfunction "D-_2") (pintype "passive"))
    )
    (net (code "244") (name "Net-(U3-V33)") (class "Default")
      (node (ref "C5") (pin "2") (pinfunction "2_2") (pintype "passive"))
      (node (ref "U3") (pin "16") (pinfunction "V33_16") (pintype "passive"))
    )
    (net (code "245") (name "VCC") (class "Default")
      (node (ref "*1") (pin "1") (pinfunction "VCC_1") (pintype "passive"))
      (node (ref "*10") (pin "1") (pinfunction "VCC_1") (pintype "passive"))
      (node (ref "*100") (pin "1") (pinfunction "VCC_1") (pintype "passive"))
      (node (ref "*101") (pin "1") (pinfunction "VCC_1") (pintype "passive"))
      (node (ref "*102") (pin "1") (pinfunction "VCC_1") (pintype "passive"))
      (node (ref "*103") (pin "1") (pinfunction "VCC_1") (pintype "passive"))
      (node (ref "*104") (pin "1") (pinfunction "VCC_1") (pintype "passive"))
      (node (ref "*11") (pin "1") (pinfunction "VCC_1") (pintype "passive"))
      (node (ref "*12") (pin "1") (pinfunction "VCC_1") (pintype "passive"))
      (node (ref "*13") (pin "1") (pinfunction "VCC_1") (pintype "passive"))
      (node (ref "*14") (pin "1") (pinfunction "VCC_1") (pintype "passive"))
      (node (ref "*15") (pin "1") (pinfunction "VCC_1") (pintype "passive"))
      (node (ref "*16") (pin "1") (pinfunction "VCC_1") (pintype "passive"))
      (node (ref "*17") (pin "1") (pinfunction "VCC_1") (pintype "passive"))
      (node (ref "*18") (pin "1") (pinfunction "VCC_1") (pintype "passive"))
      (node (ref "*19") (pin "1") (pinfunction "VCC_1") (pintype "passive"))
      (node (ref "*2") (pin "1") (pinfunction "VCC_1") (pintype "passive"))
      (node (ref "*20") (pin "1") (pinfunction "VCC_1") (pintype "passive"))
      (node (ref "*21") (pin "1") (pinfunction "VCC_1") (pintype "passive"))
      (node (ref "*22") (pin "1") (pinfunction "VCC_1") (pintype "passive"))
      (node (ref "*23") (pin "1") (pinfunction "VCC_1") (pintype "passive"))
      (node (ref "*24") (pin "1") (pinfunction "VCC_1") (pintype "passive"))
      (node (ref "*25") (pin "1") (pinfunction "VCC_1") (pintype "passive"))
      (node (ref "*26") (pin "1") (pinfunction "VCC_1") (pintype "passive"))
      (node (ref "*27") (pin "1") (pinfunction "VCC_1") (pintype "passive"))
      (node (ref "*28") (pin "1") (pinfunction "VCC_1") (pintype "passive"))
      (node (ref "*29") (pin "1") (pinfunction "VCC_1") (pintype "passive"))
      (node (ref "*3") (pin "1") (pinfunction "VCC_1") (pintype "passive"))
      (node (ref "*30") (pin "1") (pinfunction "VCC_1") (pintype "passive"))
      (node (ref "*31") (pin "1") (pinfunction "VCC_1") (pintype "passive"))
      (node (ref "*32") (pin "1") (pinfunction "VCC_1") (pintype "passive"))
      (node (ref "*33") (pin "1") (pinfunction "VCC_1") (pintype "passive"))
      (node (ref "*34") (pin "1") (pinfunction "VCC_1") (pintype "passive"))
      (node (ref "*35") (pin "1") (pinfunction "VCC_1") (pintype "passive"))
      (node (ref "*36") (pin "1") (pinfunction "VCC_1") (pintype "passive"))
      (node (ref "*37") (pin "1") (pinfunction "VCC_1") (pintype "passive"))
      (node (ref "*38") (pin "1") (pinfunction "VCC_1") (pintype "passive"))
      (node (ref "*39") (pin "1") (pinfunction "VCC_1") (pintype "passive"))
      (node (ref "*4") (pin "1") (pinfunction "VCC_1") (pintype "passive"))
      (node (ref "*40") (pin "1") (pinfunction "VCC_1") (pintype "passive"))
      (node (ref "*41") (pin "1") (pinfunction "VCC_1") (pintype "passive"))
      (node (ref "*42") (pin "1") (pinfunction "VCC_1") (pintype "passive"))
      (node (ref "*43") (pin "1") (pinfunction "VCC_1") (pintype "passive"))
      (node (ref "*44") (pin "1") (pinfunction "VCC_1") (pintype "passive"))
      (node (ref "*45") (pin "1") (pinfunction "VCC_1") (pintype "passive"))
      (node (ref "*46") (pin "1") (pinfunction "VCC_1") (pintype "passive"))
      (node (ref "*47") (pin "1") (pinfunction "VCC_1") (pintype "passive"))
      (node (ref "*48") (pin "1") (pinfunction "VCC_1") (pintype "passive"))
      (node (ref "*49") (pin "1") (pinfunction "VCC_1") (pintype "passive"))
      (node (ref "*5") (pin "1") (pinfunction "VCC_1") (pintype "passive"))
      (node (ref "*50") (pin "1") (pinfunction "VCC_1") (pintype "passive"))
      (node (ref "*51") (pin "1") (pinfunction "VCC_1") (pintype "passive"))
      (node (ref "*52") (pin "1") (pinfunction "VCC_1") (pintype "passive"))
      (node (ref "*53") (pin "1") (pinfunction "VCC_1") (pintype "passive"))
      (node (ref "*54") (pin "1") (pinfunction "VCC_1") (pintype "passive"))
      (node (ref "*55") (pin "1") (pinfunction "VCC_1") (pintype "passive"))
      (node (ref "*56") (pin "1") (pinfunction "VCC_1") (pintype "passive"))
      (node (ref "*57") (pin "1") (pinfunction "VCC_1") (pintype "passive"))
      (node (ref "*58") (pin "1") (pinfunction "VCC_1") (pintype "passive"))
      (node (ref "*59") (pin "1") (pinfunction "VCC_1") (pintype "passive"))
      (node (ref "*6") (pin "1") (pinfunction "VCC_1") (pintype "passive"))
      (node (ref "*60") (pin "1") (pinfunction "VCC_1") (pintype "passive"))
      (node (ref "*61") (pin "1") (pinfunction "VCC_1") (pintype "passive"))
      (node (ref "*62") (pin "1") (pinfunction "VCC_1") (pintype "passive"))
      (node (ref "*63") (pin "1") (pinfunction "VCC_1") (pintype "passive"))
      (node (ref "*64") (pin "1") (pinfunction "VCC_1") (pintype "passive"))
      (node (ref "*65") (pin "1") (pinfunction "VCC_1") (pintype "passive"))
      (node (ref "*66") (pin "1") (pinfunction "VCC_1") (pintype "passive"))
      (node (ref "*67") (pin "1") (pinfunction "VCC_1") (pintype "passive"))
      (node (ref "*68") (pin "1") (pinfunction "VCC_1") (pintype "passive"))
      (node (ref "*69") (pin "1") (pinfunction "VCC_1") (pintype "passive"))
      (node (ref "*7") (pin "1") (pinfunction "VCC_1") (pintype "passive"))
      (node (ref "*70") (pin "1") (pinfunction "VCC_1") (pintype "passive"))
      (node (ref "*71") (pin "1") (pinfunction "VCC_1") (pintype "passive"))
      (node (ref "*72") (pin "1") (pinfunction "VCC_1") (pintype "passive"))
      (node (ref "*73") (pin "1") (pinfunction "VCC_1") (pintype "passive"))
      (node (ref "*74") (pin "1") (pinfunction "VCC_1") (pintype "passive"))
      (node (ref "*75") (pin "1") (pinfunction "VCC_1") (pintype "passive"))
      (node (ref "*76") (pin "1") (pinfunction "VCC_1") (pintype "passive"))
      (node (ref "*77") (pin "1") (pinfunction "VCC_1") (pintype "passive"))
      (node (ref "*78") (pin "1") (pinfunction "VCC_1") (pintype "passive"))
      (node (ref "*79") (pin "1") (pinfunction "VCC_1") (pintype "passive"))
      (node (ref "*8") (pin "1") (pinfunction "VCC_1") (pintype "passive"))
      (node (ref "*80") (pin "1") (pinfunction "VCC_1") (pintype "passive"))
      (node (ref "*81") (pin "1") (pinfunction "VCC_1") (pintype "passive"))
      (node (ref "*82") (pin "1") (pinfunction "VCC_1") (pintype "passive"))
      (node (ref "*83") (pin "1") (pinfunction "VCC_1") (pintype "passive"))
      (node (ref "*84") (pin "1") (pinfunction "VCC_1") (pintype "passive"))
      (node (ref "*85") (pin "1") (pinfunction "VCC_1") (pintype "passive"))
      (node (ref "*86") (pin "1") (pinfunction "VCC_1") (pintype "passive"))
      (node (ref "*87") (pin "1") (pinfunction "VCC_1") (pintype "passive"))
      (node (ref "*88") (pin "1") (pinfunction "VCC_1") (pintype "passive"))
      (node (ref "*89") (pin "1") (pinfunction "VCC_1") (pintype "passive"))
      (node (ref "*9") (pin "1") (pinfunction "VCC_1") (pintype "passive"))
      (node (ref "*90") (pin "1") (pinfunction "VCC_1") (pintype "passive"))
      (node (ref "*91") (pin "1") (pinfunction "VCC_1") (pintype "passive"))
      (node (ref "*92") (pin "1") (pinfunction "VCC_1") (pintype "passive"))
      (node (ref "*93") (pin "1") (pinfunction "VCC_1") (pintype "passive"))
      (node (ref "*94") (pin "1") (pinfunction "VCC_1") (pintype "passive"))
      (node (ref "*95") (pin "1") (pinfunction "VCC_1") (pintype "passive"))
      (node (ref "*96") (pin "1") (pinfunction "VCC_1") (pintype "passive"))
      (node (ref "*97") (pin "1") (pinfunction "VCC_1") (pintype "passive"))
      (node (ref "*98") (pin "1") (pinfunction "VCC_1") (pintype "passive"))
      (node (ref "*99") (pin "1") (pinfunction "VCC_1") (pintype "passive"))
      (node (ref "C1") (pin "2") (pinfunction "2_2") (pintype "passive"))
      (node (ref "C2") (pin "2") (pinfunction "2_2") (pintype "passive"))
      (node (ref "C3") (pin "2") (pinfunction "2_2") (pintype "passive"))
      (node (ref "C4") (pin "2") (pinfunction "2_2") (pintype "passive"))
      (node (ref "C6") (pin "2") (pinfunction "2_2") (pintype "passive"))
      (node (ref "C7") (pin "2") (pinfunction "2_2") (pintype "passive"))
      (node (ref "C8") (pin "1") (pinfunction "1_1") (pintype "passive"))
      (node (ref "U1") (pin "14") (pinfunction "VCC_14") (pintype "passive"))
      (node (ref "U2") (pin "2") (pinfunction "VCC_2") (pintype "passive"))
      (node (ref "U3") (pin "15") (pinfunction "VCC_15") (pintype "passive"))
      (node (ref "U5") (pin "3") (pinfunction "VIN_3") (pintype "passive"))
      (node (ref "U7") (pin "1") (pinfunction "5V_1") (pintype "passive"))
      (node (ref "U8") (pin "1") (pinfunction "5V_1") (pintype "passive"))
      (node (ref "U9") (pin "1") (pinfunction "OUT-5V_1") (pintype "passive"))
    )
    (net (code "246") (name "unconnected-(R1-ALED-Pad15)") (class "Default")
      (node (ref "R1") (pin "15") (pinfunction "ALED_15") (pintype "passive"))
    )
    (net (code "247") (name "unconnected-(R1-CTS-Pad3)") (class "Default")
      (node (ref "R1") (pin "3") (pinfunction "CTS_3") (pintype "passive"))
    )
    (net (code "248") (name "unconnected-(R1-IO1-Pad20)") (class "Default")
      (node (ref "R1") (pin "20") (pinfunction "IO1_20") (pintype "passive"))
    )
    (net (code "249") (name "unconnected-(R1-IO2-Pad19)") (class "Default")
      (node (ref "R1") (pin "19") (pinfunction "IO2_19") (pintype "passive"))
    )
    (net (code "250") (name "unconnected-(R1-IO3-Pad18)") (class "Default")
      (node (ref "R1") (pin "18") (pinfunction "IO3_18") (pintype "passive"))
    )
    (net (code "251") (name "unconnected-(R1-NULL-Pad5)") (class "Default")
      (node (ref "R1") (pin "5") (pinfunction "NULL_5") (pintype "passive"))
    )
    (net (code "252") (name "unconnected-(R1-NULL-Pad6)") (class "Default")
      (node (ref "R1") (pin "6") (pinfunction "NULL_6") (pintype "passive"))
    )
    (net (code "253") (name "unconnected-(R1-NULL-Pad21)") (class "Default")
      (node (ref "R1") (pin "21") (pinfunction "NULL_21") (pintype "passive"))
    )
    (net (code "254") (name "unconnected-(R1-NULL-Pad22)") (class "Default")
      (node (ref "R1") (pin "22") (pinfunction "NULL_22") (pintype "passive"))
    )
    (net (code "255") (name "unconnected-(R1-NULL-Pad23)") (class "Default")
      (node (ref "R1") (pin "23") (pinfunction "NULL_23") (pintype "passive"))
    )
    (net (code "256") (name "unconnected-(R1-NULL-Pad24)") (class "Default")
      (node (ref "R1") (pin "24") (pinfunction "NULL_24") (pintype "passive"))
    )
    (net (code "257") (name "unconnected-(R1-NULL-Pad25)") (class "Default")
      (node (ref "R1") (pin "25") (pinfunction "NULL_25") (pintype "passive"))
    )
    (net (code "258") (name "unconnected-(R1-PWM1-Pad7)") (class "Default")
      (node (ref "R1") (pin "7") (pinfunction "PWM1_7") (pintype "passive"))
    )
    (net (code "259") (name "unconnected-(R1-PWM2-Pad8)") (class "Default")
      (node (ref "R1") (pin "8") (pinfunction "PWM2_8") (pintype "passive"))
    )
    (net (code "260") (name "unconnected-(R1-PWM3-Pad9)") (class "Default")
      (node (ref "R1") (pin "9") (pinfunction "PWM3_9") (pintype "passive"))
    )
    (net (code "261") (name "unconnected-(R1-PWM4-Pad10)") (class "Default")
      (node (ref "R1") (pin "10") (pinfunction "PWM4_10") (pintype "passive"))
    )
    (net (code "262") (name "unconnected-(R1-PWRC-Pad14)") (class "Default")
      (node (ref "R1") (pin "14") (pinfunction "PWRC_14") (pintype "passive"))
    )
    (net (code "263") (name "unconnected-(R1-RESET-Pad11)") (class "Default")
      (node (ref "R1") (pin "11") (pinfunction "RESET_11") (pintype "passive"))
    )
    (net (code "264") (name "unconnected-(R1-RTS-Pad4)") (class "Default")
      (node (ref "R1") (pin "4") (pinfunction "RTS_4") (pintype "passive"))
    )
    (net (code "265") (name "unconnected-(R1-SELECT-Pad17)") (class "Default")
      (node (ref "R1") (pin "17") (pinfunction "SELECT_17") (pintype "passive"))
    )
    (net (code "266") (name "unconnected-(R1-STAT-Pad16)") (class "Default")
      (node (ref "R1") (pin "16") (pinfunction "STAT_16") (pintype "passive"))
    )
    (net (code "267") (name "unconnected-(U1-MISO{slash}ADC4{slash}P1.4-Pad9)") (class "Default")
      (node (ref "U1") (pin "9") (pinfunction "MISO/ADC4/P1.4_9") (pintype "passive"))
    )
    (net (code "268") (name "unconnected-(U1-P0.2-Pad42)") (class "Default")
      (node (ref "U1") (pin "42") (pinfunction "P0.2_42") (pintype "passive"))
    )
    (net (code "269") (name "unconnected-(U1-P0.3-Pad43)") (class "Default")
      (node (ref "U1") (pin "43") (pinfunction "P0.3_43") (pintype "passive"))
    )
    (net (code "270") (name "unconnected-(U1-P0.7-Pad3)") (class "Default")
      (node (ref "U1") (pin "3") (pinfunction "P0.7_3") (pintype "passive"))
    )
    (net (code "271") (name "unconnected-(U1-P1.2-Pad7)") (class "Default")
      (node (ref "U1") (pin "7") (pinfunction "P1.2_7") (pintype "passive"))
    )
    (net (code "272") (name "unconnected-(U1-P1.3-Pad8)") (class "Default")
      (node (ref "U1") (pin "8") (pinfunction "P1.3_8") (pintype "passive"))
    )
    (net (code "273") (name "unconnected-(U1-P1.7{slash}TxD_3{slash}XTAL1-Pad12)") (class "Default")
      (node (ref "U1") (pin "12") (pinfunction "P1.7/TxD_3/XTAL1_12") (pintype "passive"))
    )
    (net (code "274") (name "unconnected-(U1-P3.2{slash}INT0-Pad20)") (class "Default")
      (node (ref "U1") (pin "20") (pinfunction "P3.2/INT0_20") (pintype "passive"))
    )
    (net (code "275") (name "unconnected-(U1-P4.0-Pad17)") (class "Default")
      (node (ref "U1") (pin "17") (pinfunction "P4.0_17") (pintype "passive"))
    )
    (net (code "276") (name "unconnected-(U1-P4.7-Pad6)") (class "Default")
      (node (ref "U1") (pin "6") (pinfunction "P4.7_6") (pintype "passive"))
    )
    (net (code "277") (name "unconnected-(U1-P5.4{slash}RST-Pad13)") (class "Default")
      (node (ref "U1") (pin "13") (pinfunction "P5.4/RST_13") (pintype "passive"))
    )
    (net (code "278") (name "unconnected-(U1-P5.5-Pad15)") (class "Default")
      (node (ref "U1") (pin "15") (pinfunction "P5.5_15") (pintype "passive"))
    )
    (net (code "279") (name "unconnected-(U1-RxD2{slash}P1.0-Pad4)") (class "Default")
      (node (ref "U1") (pin "4") (pinfunction "RxD2/P1.0_4") (pintype "passive"))
    )
    (net (code "280") (name "unconnected-(U1-SCLKP1.5-Pad10)") (class "Default")
      (node (ref "U1") (pin "10") (pinfunction "SCLKP1.5_10") (pintype "passive"))
    )
    (net (code "281") (name "unconnected-(U1-TxD2{slash}P1.1-Pad5)") (class "Default")
      (node (ref "U1") (pin "5") (pinfunction "TxD2/P1.1_5") (pintype "passive"))
    )
    (net (code "282") (name "unconnected-(U1-XTAL2{slash}RxD_3P1.6-Pad11)") (class "Default")
      (node (ref "U1") (pin "11") (pinfunction "XTAL2/RxD_3P1.6_11") (pintype "passive"))
    )
    (net (code "283") (name "unconnected-(U2-P3.4-Pad1)") (class "Default")
      (node (ref "U2") (pin "1") (pinfunction "P3.4_1") (pintype "passive"))
    )
    (net (code "284") (name "unconnected-(U2-P3.5-Pad3)") (class "Default")
      (node (ref "U2") (pin "3") (pinfunction "P3.5_3") (pintype "passive"))
    )
    (net (code "285") (name "unconnected-(U3-ACT#-Pad1)") (class "Default")
      (node (ref "U3") (pin "1") (pinfunction "ACT#_1") (pintype "passive"))
    )
    (net (code "286") (name "unconnected-(U3-CFG0-Pad4)") (class "Default")
      (node (ref "U3") (pin "4") (pinfunction "CFG0_4") (pintype "passive"))
    )
    (net (code "287") (name "unconnected-(U3-CFG1-Pad5)") (class "Default")
      (node (ref "U3") (pin "5") (pinfunction "CFG1_5") (pintype "passive"))
    )
    (net (code "288") (name "unconnected-(U3-IO0-Pad10)") (class "Default")
      (node (ref "U3") (pin "10") (pinfunction "IO0_10") (pintype "passive"))
    )
    (net (code "289") (name "unconnected-(U3-IO1-Pad11)") (class "Default")
      (node (ref "U3") (pin "11") (pinfunction "IO1_11") (pintype "passive"))
    )
    (net (code "290") (name "unconnected-(U3-MODE0-Pad2)") (class "Default")
      (node (ref "U3") (pin "2") (pinfunction "MODE0_2") (pintype "passive"))
    )
    (net (code "291") (name "unconnected-(U3-MODE1-Pad3)") (class "Default")
      (node (ref "U3") (pin "3") (pinfunction "MODE1_3") (pintype "passive"))
    )
    (net (code "292") (name "unconnected-(U3-RST-Pad6)") (class "Default")
      (node (ref "U3") (pin "6") (pinfunction "RST_6") (pintype "passive"))
    )
    (net (code "293") (name "unconnected-(U3-UP-Pad9)") (class "Default")
      (node (ref "U3") (pin "9") (pinfunction "UP_9") (pintype "passive"))
    )
    (net (code "294") (name "unconnected-(U9-bat-Pad3)") (class "Default")
      (node (ref "U9") (pin "3") (pinfunction "bat_3") (pintype "passive"))
    )
    (net (code "295") (name "unconnected-(U9-gnd-Pad4)") (class "Default")
      (node (ref "U9") (pin "4") (pinfunction "gnd_4") (pintype "passive"))
    )
  )
)
